# module_vs1053.net
KiCad netlist of a schematic drawn in EAGLE
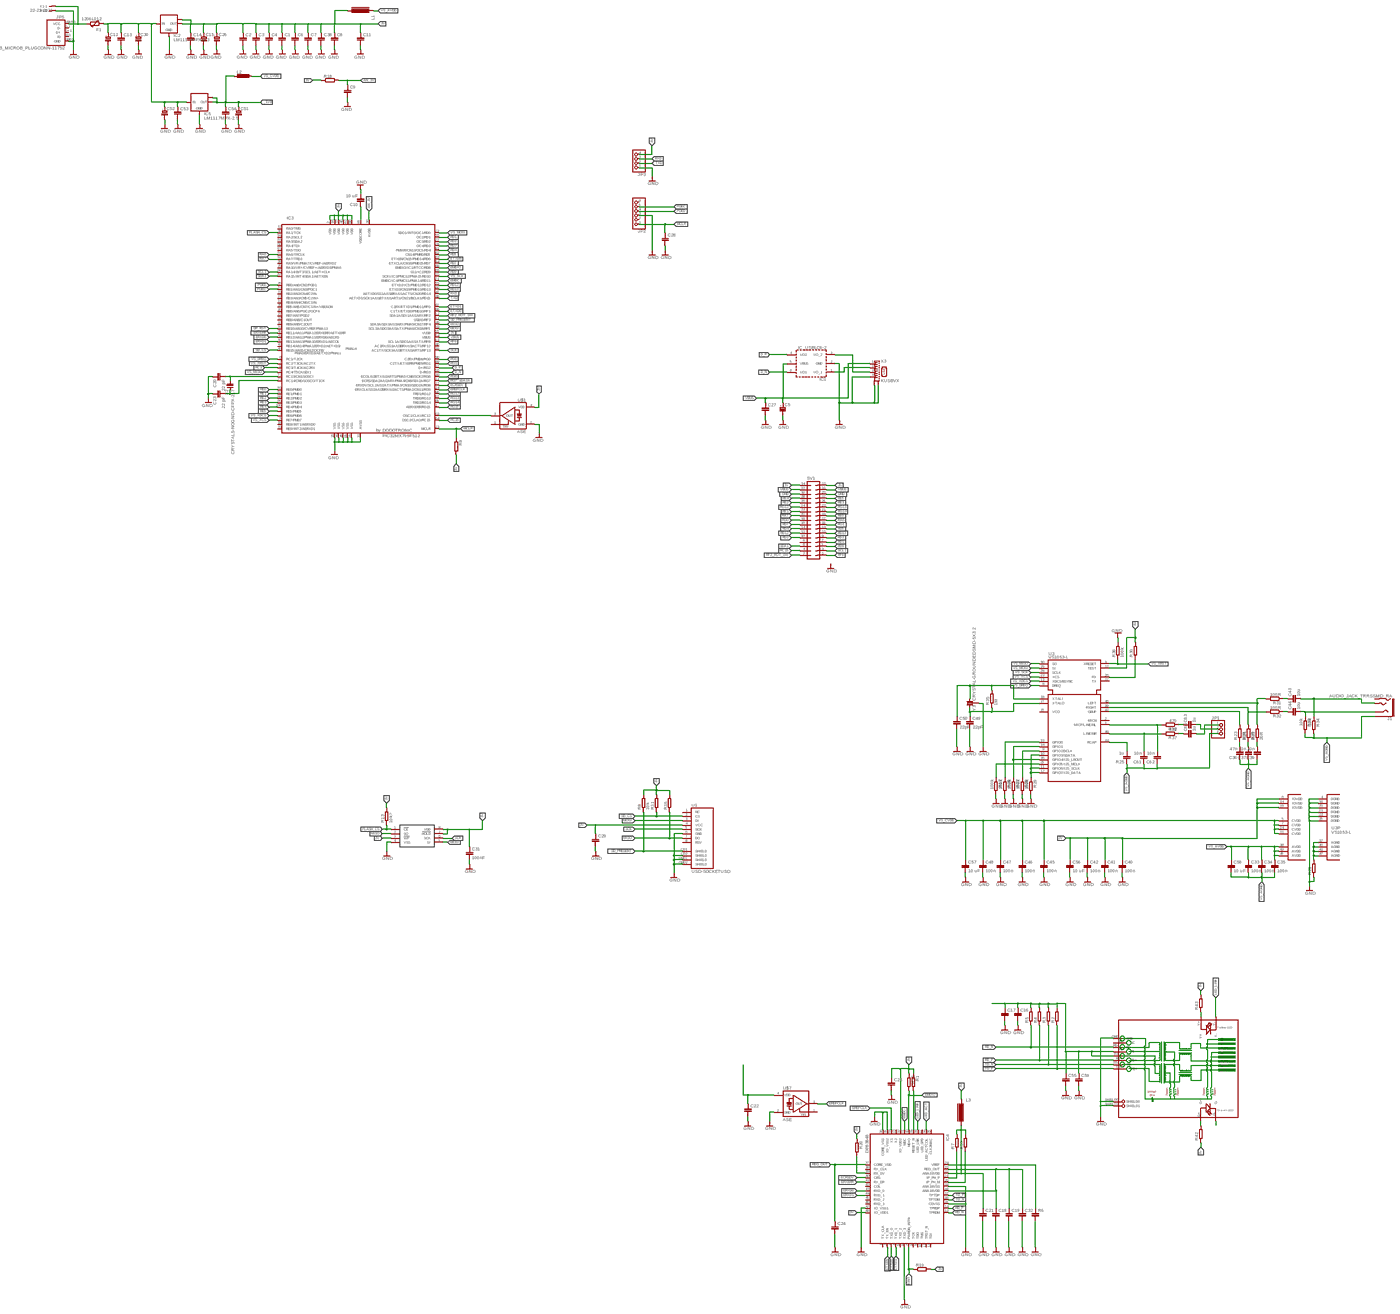
[diagram p0: schematic, sheet 1, overview]
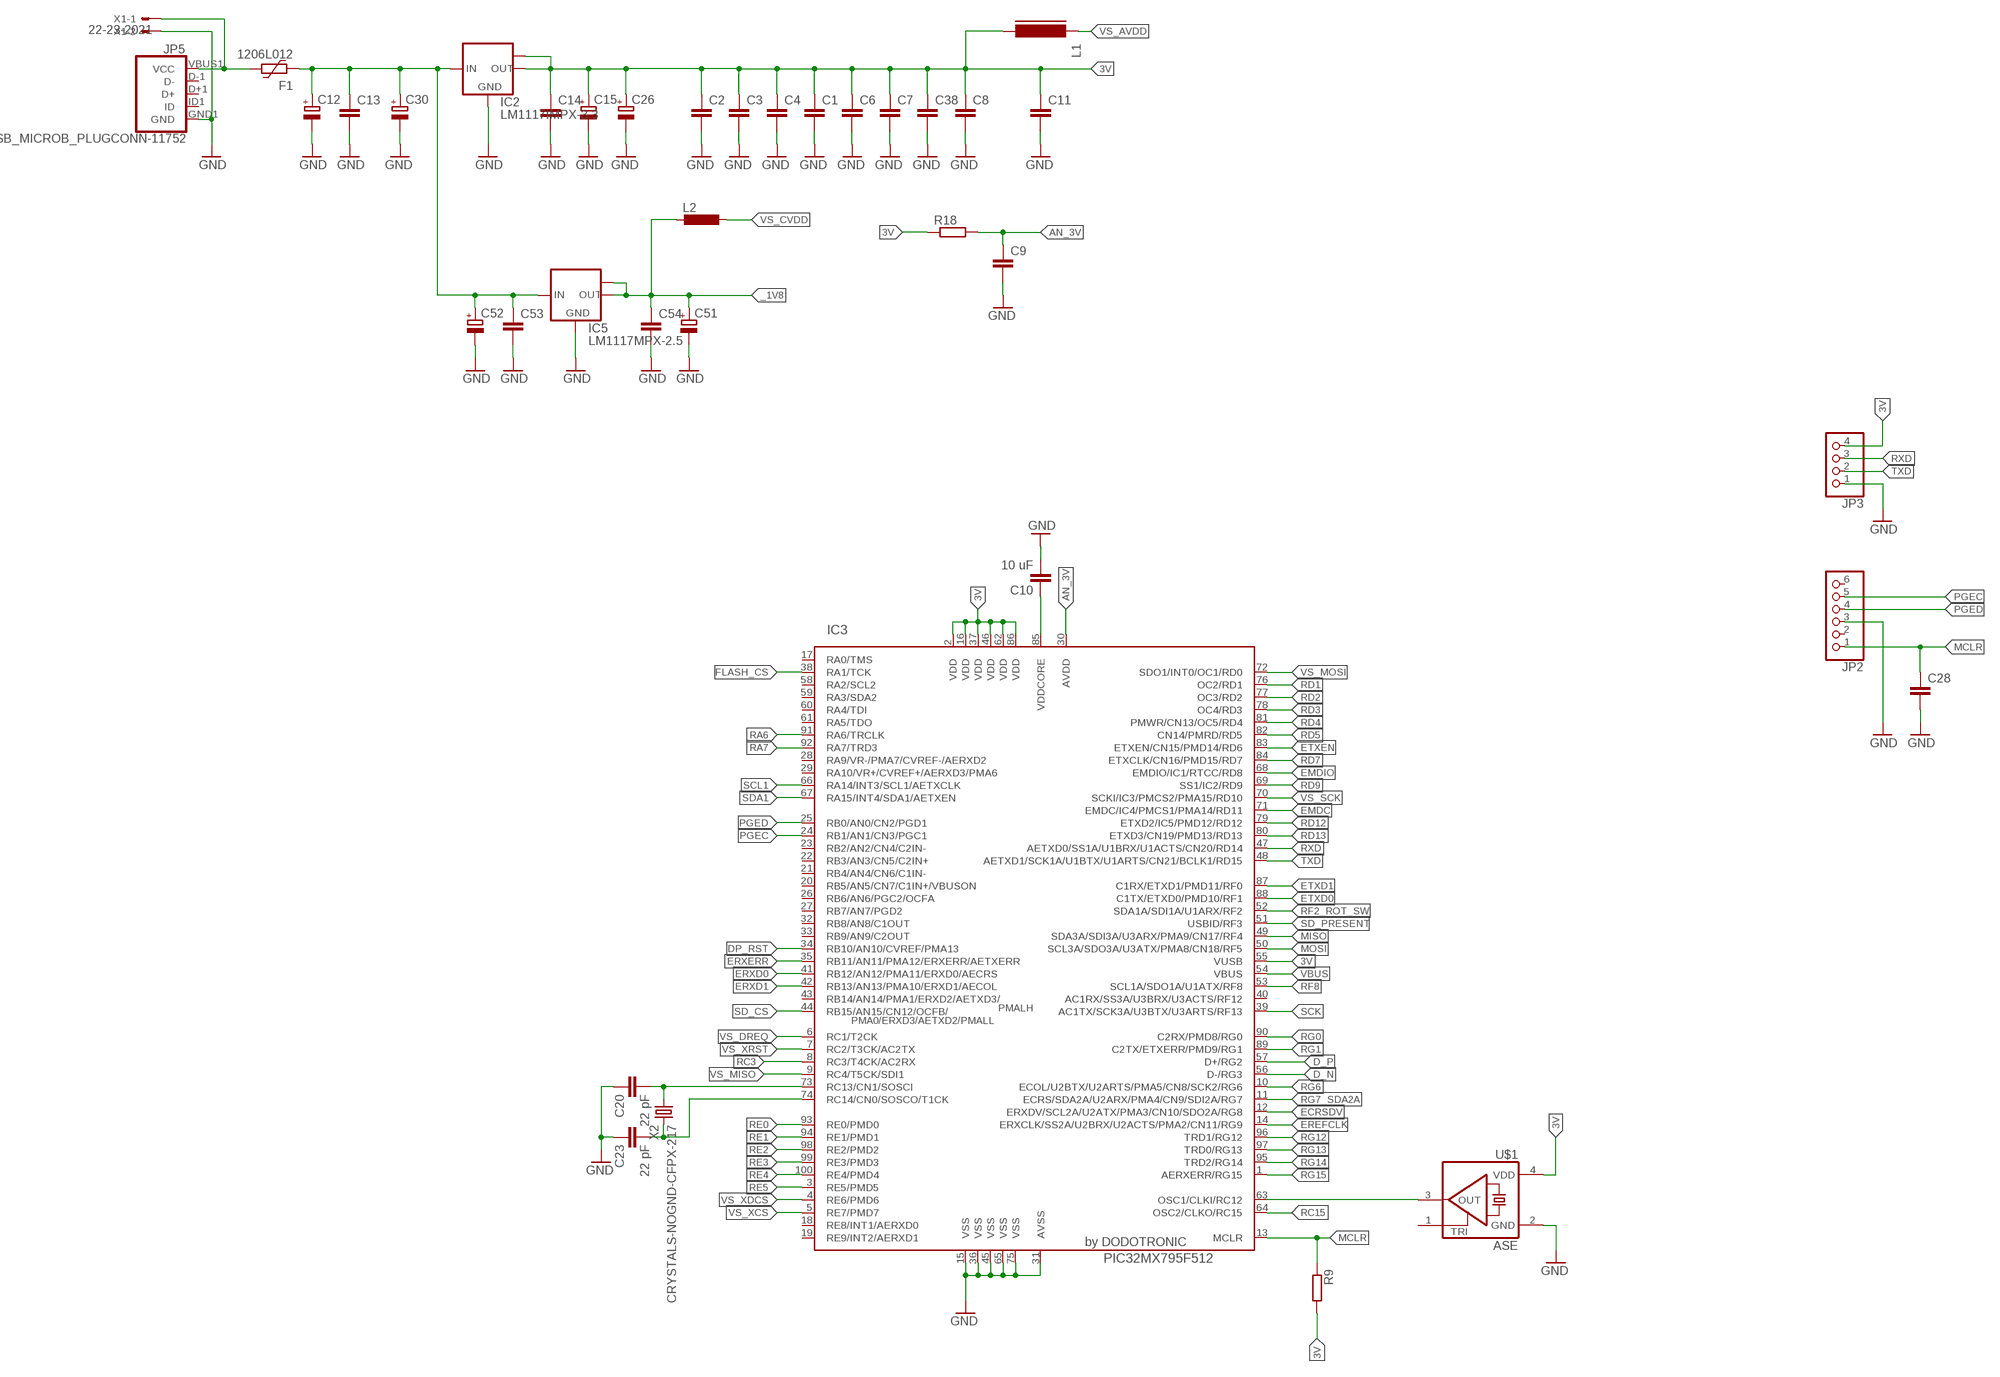
[diagram p1: schematic, sheet 1, part 1 of 4]
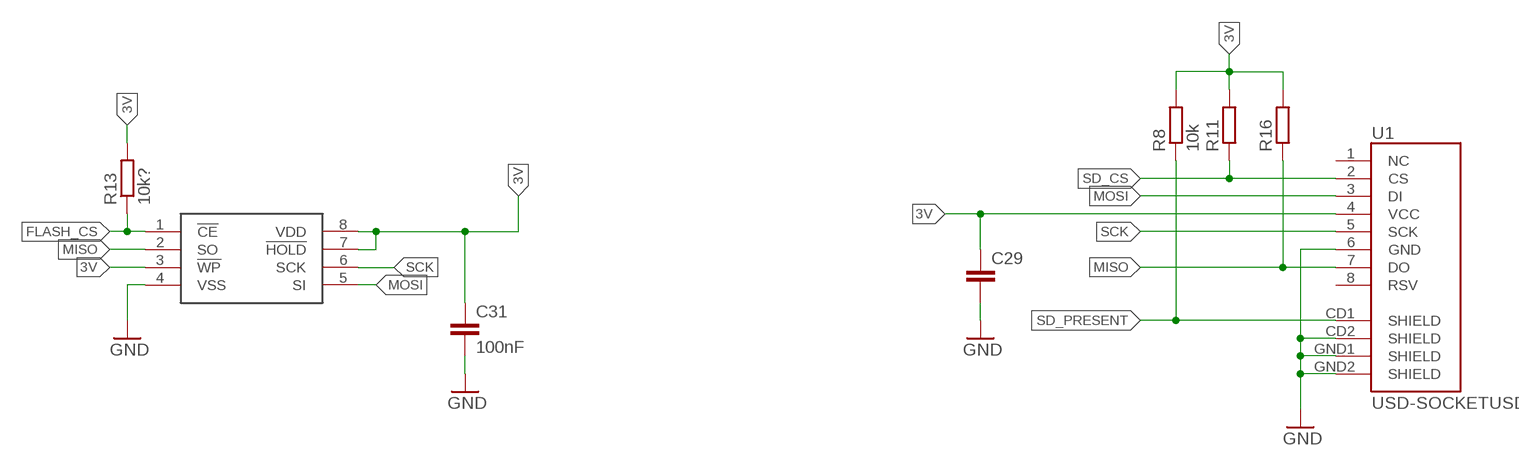
[diagram p2: schematic, sheet 1, part 2 of 4]
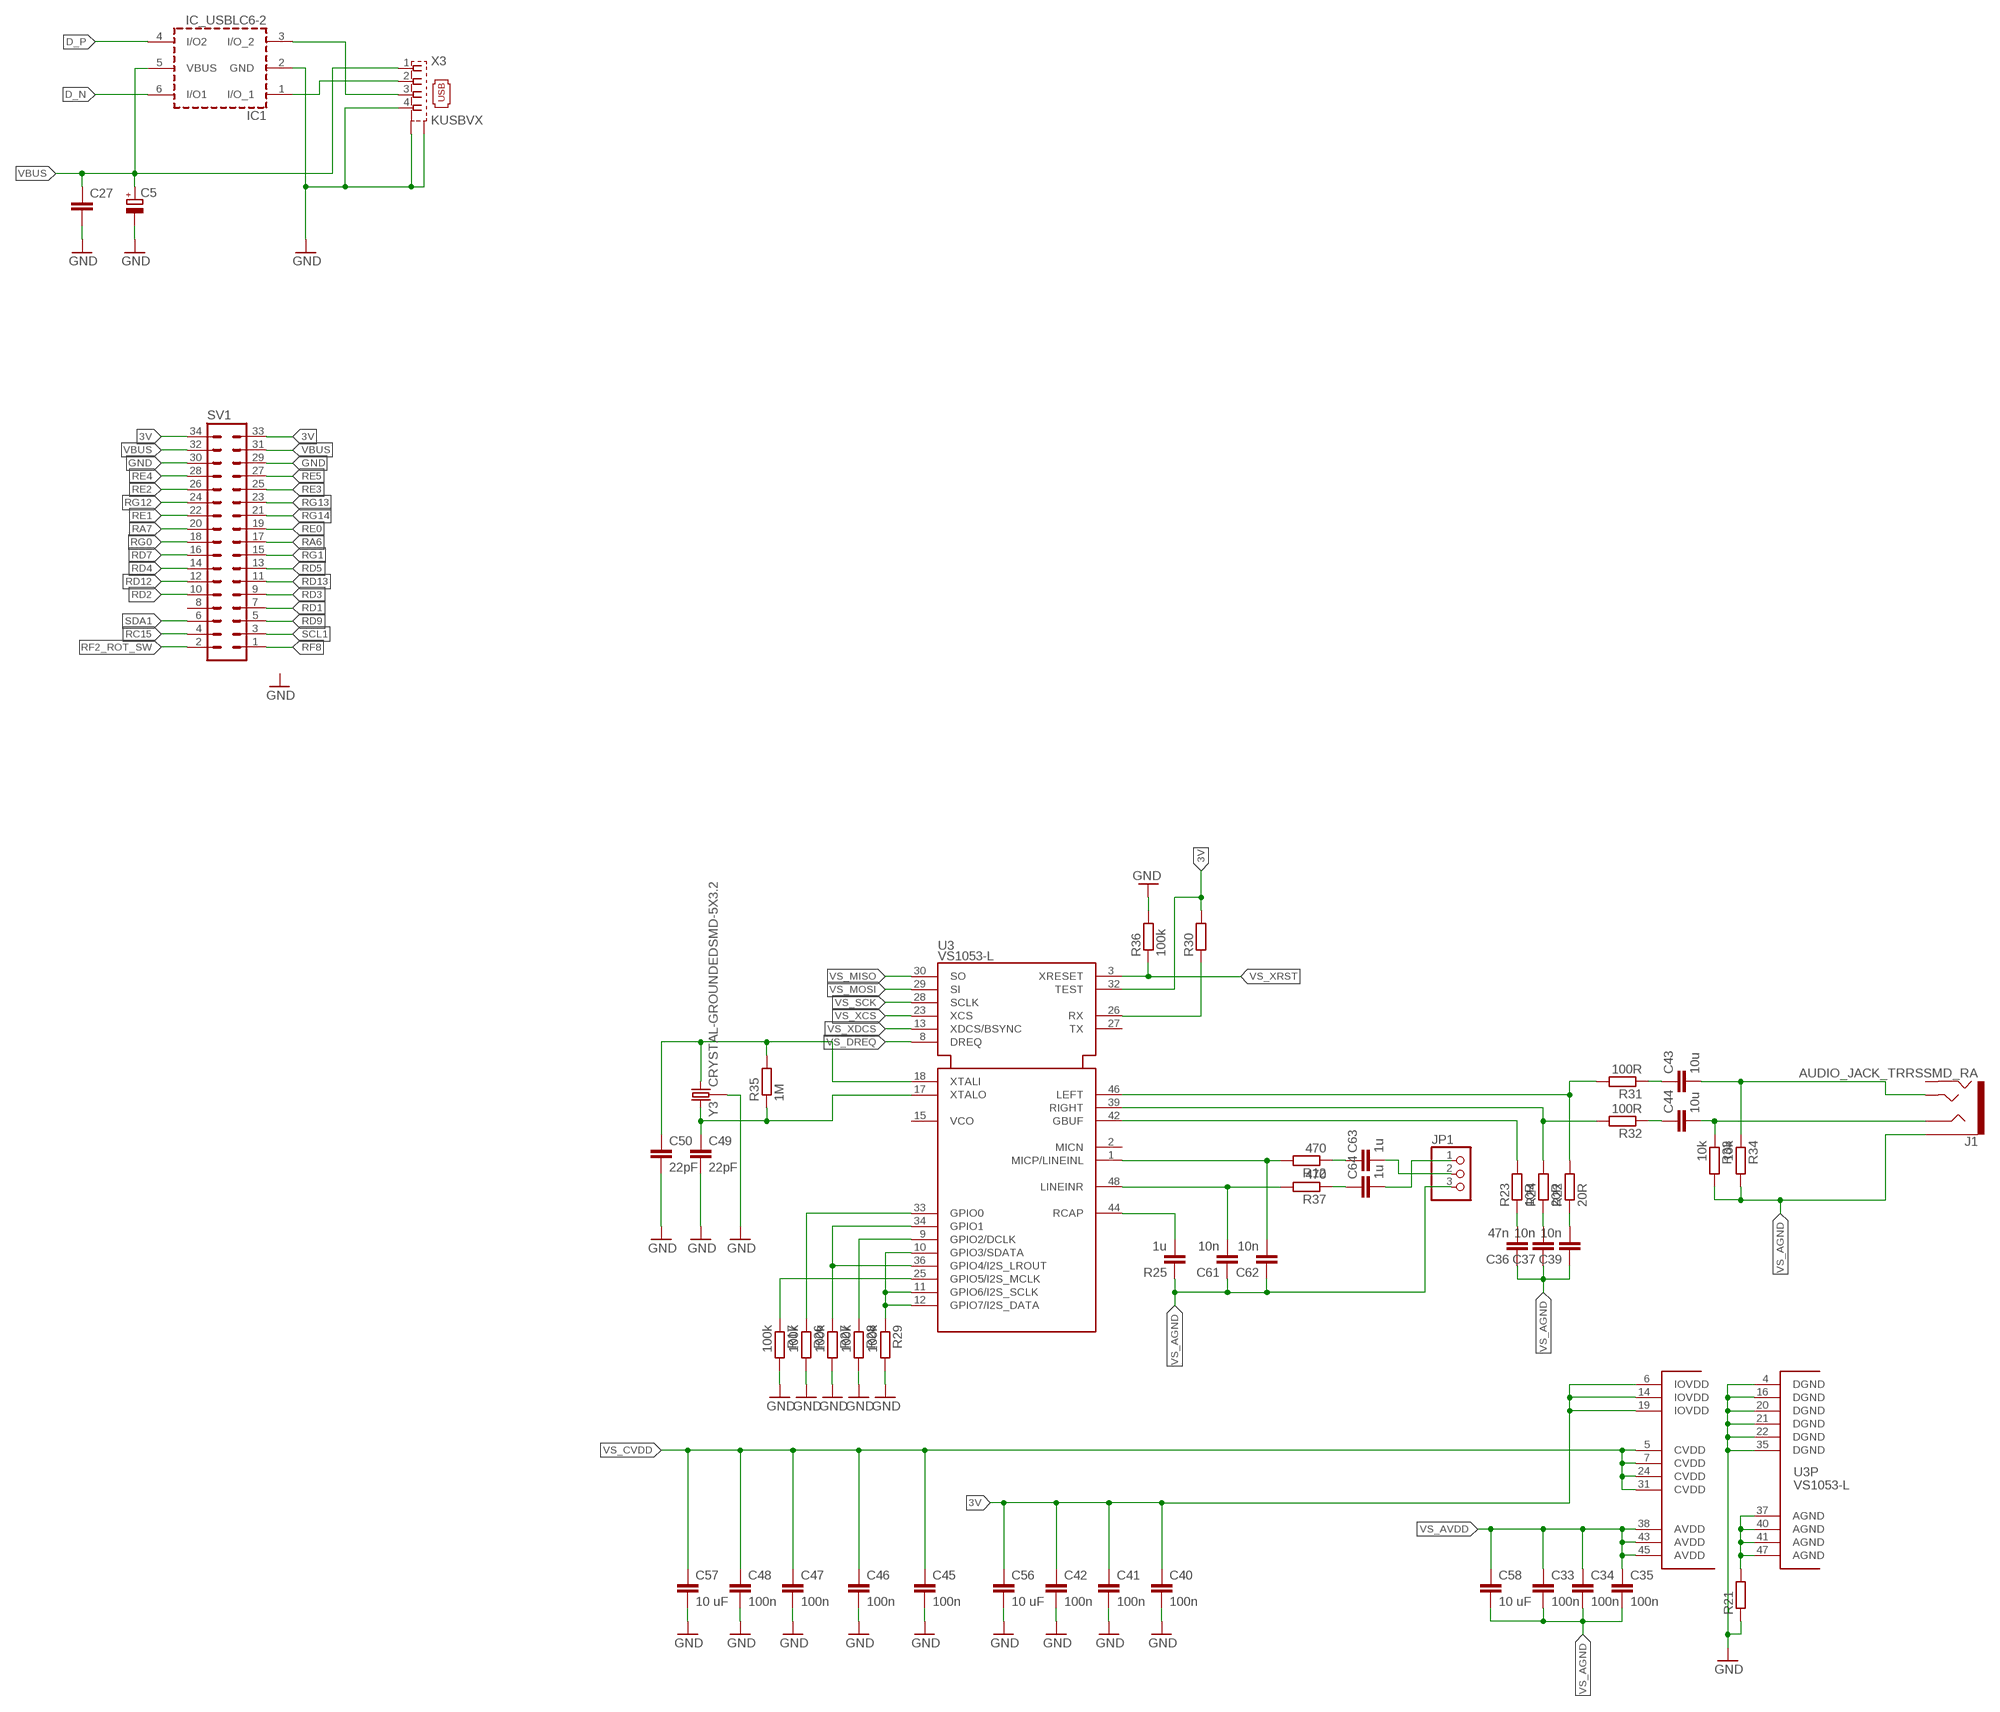
[diagram p3: schematic, sheet 1, part 3 of 4]
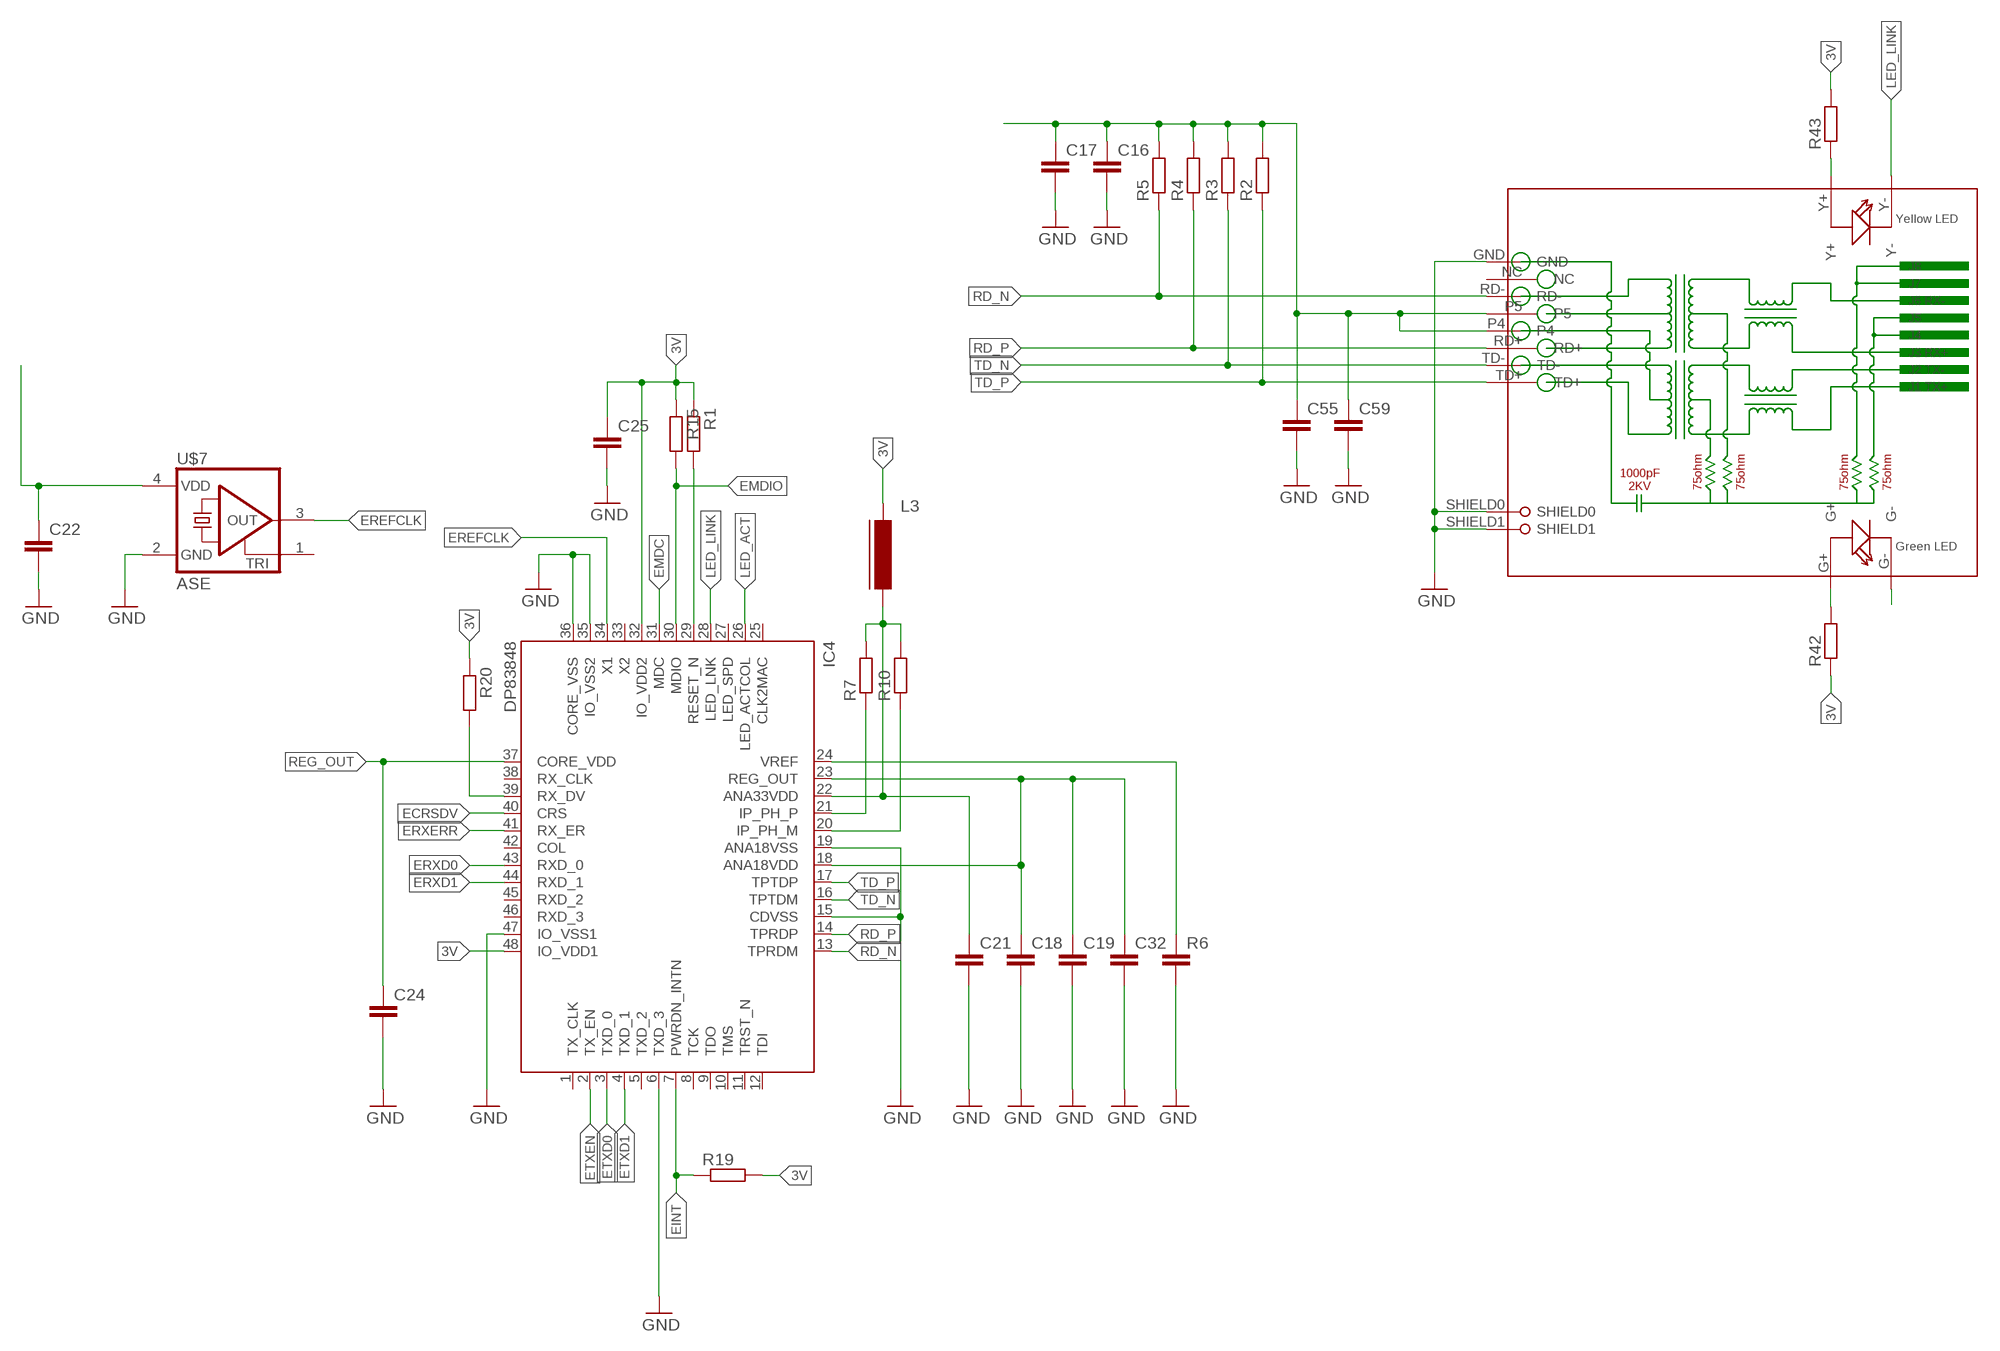
[diagram p4: schematic, sheet 1, part 4 of 4]

(export (version "E")
  (design (tool "Eeschema 10.0.6"))
  (components
    (comp (ref "C1")
      (value "C-EUC0402")
      (footprint "eagle-import:C0402")
      (libsource (lib "eagle-import") (part "C-EUC0402"))
    )
    (comp (ref "C2")
      (value "C-EUC0402")
      (footprint "eagle-import:C0402")
      (libsource (lib "eagle-import") (part "C-EUC0402"))
    )
    (comp (ref "C3")
      (value "C-EUC0402")
      (footprint "eagle-import:C0402")
      (libsource (lib "eagle-import") (part "C-EUC0402"))
    )
    (comp (ref "C4")
      (value "C-EUC0402")
      (footprint "eagle-import:C0402")
      (libsource (lib "eagle-import") (part "C-EUC0402"))
    )
    (comp (ref "C5")
      (value "CPOL-EUSMCA")
      (footprint "eagle-import:SMC_A")
      (libsource (lib "eagle-import") (part "CPOL-EUSMCA"))
    )
    (comp (ref "C6")
      (value "C-EUC0402")
      (footprint "eagle-import:C0402")
      (libsource (lib "eagle-import") (part "C-EUC0402"))
    )
    (comp (ref "C7")
      (value "C-EUC0402")
      (footprint "eagle-import:C0402")
      (libsource (lib "eagle-import") (part "C-EUC0402"))
    )
    (comp (ref "C8")
      (value "C-EUC0402")
      (footprint "eagle-import:C0402")
      (libsource (lib "eagle-import") (part "C-EUC0402"))
    )
    (comp (ref "C9")
      (value "C-EUC0402")
      (footprint "eagle-import:C0402")
      (libsource (lib "eagle-import") (part "C-EUC0402"))
    )
    (comp (ref "C10")
      (value "10 uF")
      (footprint "eagle-import:C0603")
      (libsource (lib "eagle-import") (part "C-EUC0603"))
    )
    (comp (ref "C11")
      (value "C-EUC0402")
      (footprint "eagle-import:C0402")
      (libsource (lib "eagle-import") (part "C-EUC0402"))
    )
    (comp (ref "C12")
      (value "CPOL-EUSMCB")
      (footprint "eagle-import:SMC_B")
      (libsource (lib "eagle-import") (part "CPOL-EUSMCB"))
    )
    (comp (ref "C13")
      (value "C-EUC0603")
      (footprint "eagle-import:C0603")
      (libsource (lib "eagle-import") (part "C-EUC0603"))
    )
    (comp (ref "C14")
      (value "C-EUC0603")
      (footprint "eagle-import:C0603")
      (libsource (lib "eagle-import") (part "C-EUC0603"))
    )
    (comp (ref "C15")
      (value "CPOL-EUSMCB")
      (footprint "eagle-import:SMC_B")
      (libsource (lib "eagle-import") (part "CPOL-EUSMCB"))
    )
    (comp (ref "C16")
      (value "C-EUC0603")
      (footprint "eagle-import:C0603")
      (libsource (lib "eagle-import") (part "C-EUC0603"))
    )
    (comp (ref "C17")
      (value "C-EUC0603")
      (footprint "eagle-import:C0603")
      (libsource (lib "eagle-import") (part "C-EUC0603"))
    )
    (comp (ref "C18")
      (value "C-EUC0402")
      (footprint "eagle-import:C0402")
      (libsource (lib "eagle-import") (part "C-EUC0402"))
    )
    (comp (ref "C19")
      (value "C-EUC0402")
      (footprint "eagle-import:C0402")
      (libsource (lib "eagle-import") (part "C-EUC0402"))
    )
    (comp (ref "C20")
      (value "22 pF")
      (footprint "eagle-import:C0603")
      (libsource (lib "eagle-import") (part "C-EUC0603"))
    )
    (comp (ref "C21")
      (value "C-EUC0402")
      (footprint "eagle-import:C0402")
      (libsource (lib "eagle-import") (part "C-EUC0402"))
    )
    (comp (ref "C22")
      (value "C-EUC0402")
      (footprint "eagle-import:C0402")
      (libsource (lib "eagle-import") (part "C-EUC0402"))
    )
    (comp (ref "C23")
      (value "22 pF")
      (footprint "eagle-import:C0603")
      (libsource (lib "eagle-import") (part "C-EUC0603"))
    )
    (comp (ref "C24")
      (value "C-EUC0603")
      (footprint "eagle-import:C0603")
      (libsource (lib "eagle-import") (part "C-EUC0603"))
    )
    (comp (ref "C25")
      (value "C-EUC0603")
      (footprint "eagle-import:C0603")
      (libsource (lib "eagle-import") (part "C-EUC0603"))
    )
    (comp (ref "C26")
      (value "CPOL-EUSMCA")
      (footprint "eagle-import:SMC_A")
      (libsource (lib "eagle-import") (part "CPOL-EUSMCA"))
    )
    (comp (ref "C27")
      (value "C-EUC0603")
      (footprint "eagle-import:C0603")
      (libsource (lib "eagle-import") (part "C-EUC0603"))
    )
    (comp (ref "C28")
      (value "C-EUC0603")
      (footprint "eagle-import:C0603")
      (libsource (lib "eagle-import") (part "C-EUC0603"))
    )
    (comp (ref "C29")
      (value "C-EUC0603")
      (footprint "eagle-import:C0603")
      (libsource (lib "eagle-import") (part "C-EUC0603"))
    )
    (comp (ref "C30")
      (value "CPOL-EUSMCA")
      (footprint "eagle-import:SMC_A")
      (libsource (lib "eagle-import") (part "CPOL-EUSMCA"))
    )
    (comp (ref "C31")
      (value "100nF")
      (footprint "eagle-import:C0603")
      (libsource (lib "eagle-import") (part "C-EUC0603"))
    )
    (comp (ref "C32")
      (value "C-EUC0603")
      (footprint "eagle-import:C0603")
      (libsource (lib "eagle-import") (part "C-EUC0603"))
    )
    (comp (ref "C33")
      (value "100n")
      (footprint "eagle-import:C0603")
      (libsource (lib "eagle-import") (part "C-EUC0603"))
    )
    (comp (ref "C34")
      (value "100n")
      (footprint "eagle-import:C0603")
      (libsource (lib "eagle-import") (part "C-EUC0603"))
    )
    (comp (ref "C35")
      (value "100n")
      (footprint "eagle-import:C0603")
      (libsource (lib "eagle-import") (part "C-EUC0603"))
    )
    (comp (ref "C36")
      (value "47n")
      (footprint "eagle-import:C0603")
      (libsource (lib "eagle-import") (part "C-EUC0603"))
    )
    (comp (ref "C37")
      (value "10n")
      (footprint "eagle-import:C0603")
      (libsource (lib "eagle-import") (part "C-EUC0603"))
    )
    (comp (ref "C38")
      (value "C-EUC0402")
      (footprint "eagle-import:C0402")
      (libsource (lib "eagle-import") (part "C-EUC0402"))
    )
    (comp (ref "C39")
      (value "10n")
      (footprint "eagle-import:C0603")
      (libsource (lib "eagle-import") (part "C-EUC0603"))
    )
    (comp (ref "C40")
      (value "100n")
      (footprint "eagle-import:C0402")
      (libsource (lib "eagle-import") (part "C-EUC0402"))
    )
    (comp (ref "C41")
      (value "100n")
      (footprint "eagle-import:C0402")
      (libsource (lib "eagle-import") (part "C-EUC0402"))
    )
    (comp (ref "C42")
      (value "100n")
      (footprint "eagle-import:C0402")
      (libsource (lib "eagle-import") (part "C-EUC0402"))
    )
    (comp (ref "C43")
      (value "10u")
      (footprint "eagle-import:C0603")
      (libsource (lib "eagle-import") (part "C-EUC0603"))
    )
    (comp (ref "C44")
      (value "10u")
      (footprint "eagle-import:C0603")
      (libsource (lib "eagle-import") (part "C-EUC0603"))
    )
    (comp (ref "C45")
      (value "100n")
      (footprint "eagle-import:C0402")
      (libsource (lib "eagle-import") (part "C-EUC0402"))
    )
    (comp (ref "C46")
      (value "100n")
      (footprint "eagle-import:C0603")
      (libsource (lib "eagle-import") (part "C-EUC0603"))
    )
    (comp (ref "C47")
      (value "100n")
      (footprint "eagle-import:C0603")
      (libsource (lib "eagle-import") (part "C-EUC0603"))
    )
    (comp (ref "C48")
      (value "100n")
      (footprint "eagle-import:C0603")
      (libsource (lib "eagle-import") (part "C-EUC0603"))
    )
    (comp (ref "C49")
      (value "22pF")
      (footprint "eagle-import:C0603")
      (libsource (lib "eagle-import") (part "C-EUC0603"))
    )
    (comp (ref "C50")
      (value "22pF")
      (footprint "eagle-import:C0603")
      (libsource (lib "eagle-import") (part "C-EUC0603"))
    )
    (comp (ref "C51")
      (value "CPOL-EUSMCB")
      (footprint "eagle-import:SMC_B")
      (libsource (lib "eagle-import") (part "CPOL-EUSMCB"))
    )
    (comp (ref "C52")
      (value "CPOL-EUSMCB")
      (footprint "eagle-import:SMC_B")
      (libsource (lib "eagle-import") (part "CPOL-EUSMCB"))
    )
    (comp (ref "C53")
      (value "C-EUC1206")
      (footprint "eagle-import:C1206")
      (libsource (lib "eagle-import") (part "C-EUC1206"))
    )
    (comp (ref "C54")
      (value "C-EUC1206")
      (footprint "eagle-import:C1206")
      (libsource (lib "eagle-import") (part "C-EUC1206"))
    )
    (comp (ref "C55")
      (value "C-EUC0603")
      (footprint "eagle-import:C0603")
      (libsource (lib "eagle-import") (part "C-EUC0603"))
    )
    (comp (ref "C56")
      (value "10 uF")
      (footprint "eagle-import:C0603")
      (libsource (lib "eagle-import") (part "C-EUC0603"))
    )
    (comp (ref "C57")
      (value "10 uF")
      (footprint "eagle-import:C0603")
      (libsource (lib "eagle-import") (part "C-EUC0603"))
    )
    (comp (ref "C58")
      (value "10 uF")
      (footprint "eagle-import:C0603")
      (libsource (lib "eagle-import") (part "C-EUC0603"))
    )
    (comp (ref "C59")
      (value "C-EUC0603")
      (footprint "eagle-import:C0603")
      (libsource (lib "eagle-import") (part "C-EUC0603"))
    )
    (comp (ref "C61")
      (value "10n")
      (footprint "eagle-import:C0603")
      (libsource (lib "eagle-import") (part "C-EUC0603"))
    )
    (comp (ref "C62")
      (value "10n")
      (footprint "eagle-import:C0603")
      (libsource (lib "eagle-import") (part "C-EUC0603"))
    )
    (comp (ref "C63")
      (value "1u")
      (footprint "eagle-import:C0603")
      (libsource (lib "eagle-import") (part "C-EUC0603"))
    )
    (comp (ref "C64")
      (value "1u")
      (footprint "eagle-import:C0603")
      (libsource (lib "eagle-import") (part "C-EUC0603"))
    )
    (comp (ref "F1")
      (value "1206L012")
      (footprint "eagle-import:1206L")
      (fields (field (name "MF") "Littelfuse"))
      (libsource (lib "eagle-import") (part "?1206L012"))
    )
    (comp (ref "IC1")
      (value "IC_USBLC6-2")
      (footprint "eagle-import:SOT-23-6L")
      (libsource (lib "eagle-import") (part "IC_USBLC6-2"))
    )
    (comp (ref "IC2")
      (value "LM1117IMPX-3.3")
      (footprint "eagle-import:SOT223")
      (libsource (lib "eagle-import") (part "LM1117IMPX-3.3"))
    )
    (comp (ref "IC3")
      (value "PIC32MX795F512")
      (footprint "eagle-import:TQFP100_12X12")
      (libsource (lib "eagle-import") (part "PIC32MX795F512"))
    )
    (comp (ref "IC4")
      (value "DP83848")
      (footprint "eagle-import:LQFP48")
      (fields (field (name "MPN") "DP83848VYB"))
      (libsource (lib "eagle-import") (part "DP83848"))
    )
    (comp (ref "IC5")
      (value "LM1117MPX-2.5")
      (footprint "eagle-import:SOT223")
      (libsource (lib "eagle-import") (part "LM1117MPX-2.5"))
    )
    (comp (ref "J1")
      (value "AUDIO_JACK_TRRSSMD_RA")
      (footprint "eagle-import:AUDIO_JACK_3.5MM_TRRS_SMD_RA")
      (libsource (lib "eagle-import") (part "AUDIO_JACK_TRRSSMD_RA"))
    )
    (comp (ref "JP1")
      (value "PINHD-1X3")
      (footprint "eagle-import:1X03")
      (libsource (lib "eagle-import") (part "PINHD-1X3"))
    )
    (comp (ref "JP2")
      (value "PINHD-1X6")
      (footprint "eagle-import:1X06")
      (libsource (lib "eagle-import") (part "PINHD-1X6"))
    )
    (comp (ref "JP3")
      (value "PINHD-1X4")
      (footprint "eagle-import:1X04")
      (libsource (lib "eagle-import") (part "PINHD-1X4"))
    )
    (comp (ref "JP5")
      (value "USB_MICROB_PLUGCONN-11752")
      (footprint "eagle-import:USB-B-MICRO-SMD_V03")
      (libsource (lib "eagle-import") (part "USB_MICROB_PLUGCONN-11752"))
    )
    (comp (ref "L1")
      (value "FERRITE-0805")
      (footprint "eagle-import:FB805")
      (libsource (lib "eagle-import") (part "FERRITE-0805"))
    )
    (comp (ref "L2")
      (value "L-EU0204/7")
      (footprint "eagle-import:0204_7")
      (libsource (lib "eagle-import") (part "L-EU0204/7"))
    )
    (comp (ref "L3")
      (value "FERRITE-0805")
      (footprint "eagle-import:FB805")
      (libsource (lib "eagle-import") (part "FERRITE-0805"))
    )
    (comp (ref "R1")
      (value "R-EU_R0402")
      (footprint "eagle-import:R0402")
      (libsource (lib "eagle-import") (part "R-EU_R0402"))
    )
    (comp (ref "R2")
      (value "R-EU_R0603")
      (footprint "eagle-import:R0603")
      (libsource (lib "eagle-import") (part "R-EU_R0603"))
    )
    (comp (ref "R3")
      (value "R-EU_R0603")
      (footprint "eagle-import:R0603")
      (libsource (lib "eagle-import") (part "R-EU_R0603"))
    )
    (comp (ref "R4")
      (value "R-EU_R0603")
      (footprint "eagle-import:R0603")
      (libsource (lib "eagle-import") (part "R-EU_R0603"))
    )
    (comp (ref "R5")
      (value "R-EU_R0603")
      (footprint "eagle-import:R0603")
      (libsource (lib "eagle-import") (part "R-EU_R0603"))
    )
    (comp (ref "R6")
      (value "C-EUC0603")
      (footprint "eagle-import:C0603")
      (libsource (lib "eagle-import") (part "C-EUC0603"))
    )
    (comp (ref "R7")
      (value "R-EU_R0402")
      (footprint "eagle-import:R0402")
      (libsource (lib "eagle-import") (part "R-EU_R0402"))
    )
    (comp (ref "R8")
      (value "10k")
      (footprint "eagle-import:R0603")
      (libsource (lib "eagle-import") (part "R-EU_R0603"))
    )
    (comp (ref "R9")
      (value "R-EU_R0603")
      (footprint "eagle-import:R0603")
      (libsource (lib "eagle-import") (part "R-EU_R0603"))
    )
    (comp (ref "R10")
      (value "R-EU_R0402")
      (footprint "eagle-import:R0402")
      (libsource (lib "eagle-import") (part "R-EU_R0402"))
    )
    (comp (ref "R11")
      (value "R-EU_R0603")
      (footprint "eagle-import:R0603")
      (libsource (lib "eagle-import") (part "R-EU_R0603"))
    )
    (comp (ref "R12")
      (value "470")
      (footprint "eagle-import:0204_7")
      (libsource (lib "eagle-import") (part "R-EU_0204/7"))
    )
    (comp (ref "R13")
      (value "10k?")
      (footprint "eagle-import:R0603")
      (libsource (lib "eagle-import") (part "R-EU_R0603"))
    )
    (comp (ref "R15")
      (value "R-EU_R0603")
      (footprint "eagle-import:R0603")
      (libsource (lib "eagle-import") (part "R-EU_R0603"))
    )
    (comp (ref "R16")
      (value "R-EU_R0603")
      (footprint "eagle-import:R0603")
      (libsource (lib "eagle-import") (part "R-EU_R0603"))
    )
    (comp (ref "R17")
      (value "100k")
      (footprint "eagle-import:R0402")
      (libsource (lib "eagle-import") (part "R-EU_R0402"))
    )
    (comp (ref "R18")
      (value "R-EU_R0805")
      (footprint "eagle-import:R0805")
      (libsource (lib "eagle-import") (part "R-EU_R0805"))
    )
    (comp (ref "R19")
      (value "R-EU_R0402")
      (footprint "eagle-import:R0402")
      (libsource (lib "eagle-import") (part "R-EU_R0402"))
    )
    (comp (ref "R20")
      (value "R-EU_R0603")
      (footprint "eagle-import:R0603")
      (libsource (lib "eagle-import") (part "R-EU_R0603"))
    )
    (comp (ref "R21")
      (value "R-EU_R0603")
      (footprint "eagle-import:R0603")
      (libsource (lib "eagle-import") (part "R-EU_R0603"))
    )
    (comp (ref "R22")
      (value "20R")
      (footprint "eagle-import:R0603")
      (libsource (lib "eagle-import") (part "R-EU_R0603"))
    )
    (comp (ref "R23")
      (value "10R")
      (footprint "eagle-import:R0603")
      (libsource (lib "eagle-import") (part "R-EU_R0603"))
    )
    (comp (ref "R24")
      (value "20R")
      (footprint "eagle-import:R0603")
      (libsource (lib "eagle-import") (part "R-EU_R0603"))
    )
    (comp (ref "R25")
      (value "1u")
      (footprint "eagle-import:C0603")
      (libsource (lib "eagle-import") (part "C-EUC0603"))
    )
    (comp (ref "R26")
      (value "100k")
      (footprint "eagle-import:R0402")
      (libsource (lib "eagle-import") (part "R-EU_R0402"))
    )
    (comp (ref "R27")
      (value "100k")
      (footprint "eagle-import:R0402")
      (libsource (lib "eagle-import") (part "R-EU_R0402"))
    )
    (comp (ref "R28")
      (value "100k")
      (footprint "eagle-import:R0402")
      (libsource (lib "eagle-import") (part "R-EU_R0402"))
    )
    (comp (ref "R29")
      (value "100k")
      (footprint "eagle-import:R0402")
      (libsource (lib "eagle-import") (part "R-EU_R0402"))
    )
    (comp (ref "R30")
      (value "R-EU_0204/7")
      (footprint "eagle-import:0204_7")
      (libsource (lib "eagle-import") (part "R-EU_0204/7"))
    )
    (comp (ref "R31")
      (value "100R")
      (footprint "eagle-import:R0603")
      (libsource (lib "eagle-import") (part "R-EU_R0603"))
    )
    (comp (ref "R32")
      (value "100R")
      (footprint "eagle-import:R0603")
      (libsource (lib "eagle-import") (part "R-EU_R0603"))
    )
    (comp (ref "R33")
      (value "10k")
      (footprint "eagle-import:R0603")
      (libsource (lib "eagle-import") (part "R-EU_R0603"))
    )
    (comp (ref "R34")
      (value "10k")
      (footprint "eagle-import:R0603")
      (libsource (lib "eagle-import") (part "R-EU_R0603"))
    )
    (comp (ref "R35")
      (value "1M")
      (footprint "eagle-import:R0603")
      (libsource (lib "eagle-import") (part "R-EU_R0603"))
    )
    (comp (ref "R36")
      (value "100k")
      (footprint "eagle-import:R0603")
      (libsource (lib "eagle-import") (part "R-EU_R0603"))
    )
    (comp (ref "R37")
      (value "470")
      (footprint "eagle-import:0204_7")
      (libsource (lib "eagle-import") (part "R-EU_0204/7"))
    )
    (comp (ref "R42")
      (value "R-EU_R0603")
      (footprint "eagle-import:R0603")
      (libsource (lib "eagle-import") (part "R-EU_R0603"))
    )
    (comp (ref "R43")
      (value "R-EU_R0603")
      (footprint "eagle-import:R0603")
      (libsource (lib "eagle-import") (part "R-EU_R0603"))
    )
    (comp (ref "RJ1")
      (value "HR911105A")
      (footprint "eagle-import:HR911105A")
      (libsource (lib "eagle-import") (part "HR911105A"))
    )
    (comp (ref "SV1")
      (value "ML34L")
      (footprint "eagle-import:ML34L")
      (libsource (lib "eagle-import") (part "ML34L"))
    )
    (comp (ref "U$1")
      (value "ASE")
      (footprint "eagle-import:ASE")
      (libsource (lib "eagle-import") (part "ASE"))
    )
    (comp (ref "U$2")
      (value "SST25VF016BSO8M")
      (footprint "eagle-import:SO-08M")
      (libsource (lib "eagle-import") (part "SST25VF016BSO8M"))
    )
    (comp (ref "U$7")
      (value "ASE")
      (footprint "eagle-import:ASE")
      (libsource (lib "eagle-import") (part "ASE"))
    )
    (comp (ref "U1")
      (value "USD-SOCKETUSD")
      (footprint "eagle-import:USD-SOCKET-PP")
      (libsource (lib "eagle-import") (part "USD-SOCKETUSD"))
    )
    (comp (ref "U3")
      (value "VS1053-L")
      (footprint "eagle-import:LQFP48")
      (libsource (lib "eagle-import") (part "VS1053-L"))
    )
    (comp (ref "X1")
      (value "22-23-2021")
      (footprint "eagle-import:22-23-2021")
      (fields (field (name "MF") "MOLEX"))
      (libsource (lib "eagle-import") (part "22-23-2021"))
    )
    (comp (ref "X2")
      (value "CRYSTALS-NOGND-CFPX-217")
      (footprint "eagle-import:3.2X1.5-2-PAD")
      (libsource (lib "eagle-import") (part "CRYSTALS-NOGND-CFPX-217"))
    )
    (comp (ref "X3")
      (value "KUSBVX")
      (footprint "eagle-import:KUSBVX")
      (libsource (lib "eagle-import") (part "KUSBVX"))
    )
    (comp (ref "Y3")
      (value "CRYSTAL-GROUNDEDSMD-5X3.2")
      (footprint "eagle-import:CRYSTAL-SMD-5X3.2-4PAD")
      (libsource (lib "eagle-import") (part "CRYSTAL-GROUNDEDSMD-5X3.2"))
    )
  )
  (nets
    (net (code "1") (name "/A3V") (class "Default")
      (node (ref "C16") (pin "1") (pinfunction "1_1") (pintype "passive"))
      (node (ref "C17") (pin "1") (pinfunction "1_1") (pintype "passive"))
      (node (ref "C21") (pin "1") (pinfunction "1_1") (pintype "passive"))
      (node (ref "C55") (pin "1") (pinfunction "1_1") (pintype "passive"))
      (node (ref "C59") (pin "1") (pinfunction "1_1") (pintype "passive"))
      (node (ref "IC4") (pin "22") (pinfunction "ANA33VDD_22") (pintype "power_in"))
      (node (ref "L3") (pin "2") (pinfunction "2_2") (pintype "passive"))
      (node (ref "R10") (pin "2") (pinfunction "2_2") (pintype "passive"))
      (node (ref "R2") (pin "2") (pinfunction "2_2") (pintype "passive"))
      (node (ref "R3") (pin "2") (pinfunction "2_2") (pintype "passive"))
      (node (ref "R4") (pin "2") (pinfunction "2_2") (pintype "passive"))
      (node (ref "R5") (pin "2") (pinfunction "2_2") (pintype "passive"))
      (node (ref "R7") (pin "2") (pinfunction "2_2") (pintype "passive"))
      (node (ref "RJ1") (pin "P4") (pinfunction "P4_P4") (pintype "bidirectional"))
      (node (ref "RJ1") (pin "P5") (pinfunction "P5_P5") (pintype "bidirectional"))
    )
    (net (code "2") (name "3V") (class "Default")
      (node (ref "C1") (pin "1") (pinfunction "1_1") (pintype "passive"))
      (node (ref "C11") (pin "1") (pinfunction "1_1") (pintype "passive"))
      (node (ref "C14") (pin "1") (pinfunction "1_1") (pintype "passive"))
      (node (ref "C15") (pin "+") (pinfunction "+_+") (pintype "passive"))
      (node (ref "C2") (pin "1") (pinfunction "1_1") (pintype "passive"))
      (node (ref "C22") (pin "1") (pinfunction "1_1") (pintype "passive"))
      (node (ref "C25") (pin "1") (pinfunction "1_1") (pintype "passive"))
      (node (ref "C26") (pin "+") (pinfunction "+_+") (pintype "passive"))
      (node (ref "C29") (pin "1") (pinfunction "1_1") (pintype "passive"))
      (node (ref "C3") (pin "1") (pinfunction "1_1") (pintype "passive"))
      (node (ref "C31") (pin "1") (pinfunction "1_1") (pintype "passive"))
      (node (ref "C38") (pin "1") (pinfunction "1_1") (pintype "passive"))
      (node (ref "C4") (pin "1") (pinfunction "1_1") (pintype "passive"))
      (node (ref "C40") (pin "1") (pinfunction "1_1") (pintype "passive"))
      (node (ref "C41") (pin "1") (pinfunction "1_1") (pintype "passive"))
      (node (ref "C42") (pin "1") (pinfunction "1_1") (pintype "passive"))
      (node (ref "C56") (pin "1") (pinfunction "1_1") (pintype "passive"))
      (node (ref "C6") (pin "1") (pinfunction "1_1") (pintype "passive"))
      (node (ref "C7") (pin "1") (pinfunction "1_1") (pintype "passive"))
      (node (ref "C8") (pin "1") (pinfunction "1_1") (pintype "passive"))
      (node (ref "IC2") (pin "2") (pinfunction "OUT_2") (pintype "passive"))
      (node (ref "IC2") (pin "TAB") (pinfunction "OUT1_TAB") (pintype "passive"))
      (node (ref "IC3") (pin "16") (pinfunction "VDD_16") (pintype "power_in"))
      (node (ref "IC3") (pin "2") (pinfunction "VDD_2") (pintype "power_in"))
      (node (ref "IC3") (pin "37") (pinfunction "VDD_37") (pintype "power_in"))
      (node (ref "IC3") (pin "46") (pinfunction "VDD_46") (pintype "power_in"))
      (node (ref "IC3") (pin "55") (pinfunction "VUSB_55") (pintype "bidirectional"))
      (node (ref "IC3") (pin "62") (pinfunction "VDD_62") (pintype "power_in"))
      (node (ref "IC3") (pin "86") (pinfunction "VDD_86") (pintype "power_in"))
      (node (ref "IC4") (pin "32") (pinfunction "IO_VDD2_32") (pintype "power_in"))
      (node (ref "IC4") (pin "48") (pinfunction "IO_VDD1_48") (pintype "power_in"))
      (node (ref "JP3") (pin "4") (pinfunction "4_4") (pintype "passive"))
      (node (ref "L1") (pin "2") (pinfunction "2_2") (pintype "passive"))
      (node (ref "L3") (pin "1") (pinfunction "1_1") (pintype "passive"))
      (node (ref "R1") (pin "1") (pinfunction "1_1") (pintype "passive"))
      (node (ref "R11") (pin "2") (pinfunction "2_2") (pintype "passive"))
      (node (ref "R13") (pin "2") (pinfunction "2_2") (pintype "passive"))
      (node (ref "R15") (pin "1") (pinfunction "1_1") (pintype "passive"))
      (node (ref "R16") (pin "2") (pinfunction "2_2") (pintype "passive"))
      (node (ref "R18") (pin "1") (pinfunction "1_1") (pintype "passive"))
      (node (ref "R19") (pin "2") (pinfunction "2_2") (pintype "passive"))
      (node (ref "R20") (pin "1") (pinfunction "1_1") (pintype "passive"))
      (node (ref "R30") (pin "2") (pinfunction "2_2") (pintype "passive"))
      (node (ref "R42") (pin "1") (pinfunction "1_1") (pintype "passive"))
      (node (ref "R43") (pin "2") (pinfunction "2_2") (pintype "passive"))
      (node (ref "R8") (pin "2") (pinfunction "2_2") (pintype "passive"))
      (node (ref "R9") (pin "2") (pinfunction "2_2") (pintype "passive"))
      (node (ref "SV1") (pin "33") (pinfunction "33_33") (pintype "passive"))
      (node (ref "SV1") (pin "34") (pinfunction "34_34") (pintype "passive"))
      (node (ref "U$1") (pin "4") (pinfunction "VDD_4") (pintype "power_in"))
      (node (ref "U$2") (pin "3") (pinfunction "~{WP}_3") (pintype "bidirectional"))
      (node (ref "U$2") (pin "7") (pinfunction "~{HOLD}_7") (pintype "bidirectional"))
      (node (ref "U$2") (pin "8") (pinfunction "VDD_8") (pintype "bidirectional"))
      (node (ref "U$7") (pin "4") (pinfunction "VDD_4") (pintype "power_in"))
      (node (ref "U1") (pin "4") (pinfunction "VCC_4") (pintype "bidirectional"))
      (node (ref "U3") (pin "14") (pinfunction "IOVDD_14") (pintype "power_in"))
      (node (ref "U3") (pin "19") (pinfunction "IOVDD_19") (pintype "power_in"))
      (node (ref "U3") (pin "32") (pinfunction "TEST_32") (pintype "input"))
      (node (ref "U3") (pin "6") (pinfunction "IOVDD_6") (pintype "power_in"))
    )
    (net (code "3") (name "AN_3V") (class "Default")
      (node (ref "C9") (pin "1") (pinfunction "1_1") (pintype "passive"))
      (node (ref "IC3") (pin "30") (pinfunction "AVDD_30") (pintype "bidirectional"))
      (node (ref "R18") (pin "2") (pinfunction "2_2") (pintype "passive"))
    )
    (net (code "4") (name "DP_RST") (class "Default")
      (node (ref "IC3") (pin "34") (pinfunction "RB10/AN10/CVREF/PMA13_34") (pintype "bidirectional"))
      (node (ref "IC4") (pin "29") (pinfunction "RESET_N_29") (pintype "input"))
      (node (ref "R1") (pin "2") (pinfunction "2_2") (pintype "passive"))
    )
    (net (code "5") (name "D_N") (class "Default")
      (node (ref "IC1") (pin "6") (pinfunction "I/O1_6") (pintype "bidirectional"))
      (node (ref "IC3") (pin "56") (pinfunction "D-/RG3_56") (pintype "bidirectional"))
    )
    (net (code "6") (name "D_P") (class "Default")
      (node (ref "IC1") (pin "4") (pinfunction "I/O2_4") (pintype "bidirectional"))
      (node (ref "IC3") (pin "57") (pinfunction "D+/RG2_57") (pintype "bidirectional"))
    )
    (net (code "7") (name "ECRSDV") (class "Default")
      (node (ref "IC3") (pin "12") (pinfunction "ERXDV/SCL2A/U2ATX/PMA3/CN10/SDO2A/RG8_12") (pintype "bidirectional"))
      (node (ref "IC4") (pin "40") (pinfunction "CRS_40") (pintype "bidirectional"))
    )
    (net (code "8") (name "EINT") (class "Default")
      (node (ref "IC4") (pin "7") (pinfunction "PWRDN_INTN_7") (pintype "bidirectional"))
      (node (ref "R19") (pin "1") (pinfunction "1_1") (pintype "passive"))
    )
    (net (code "9") (name "EMDC") (class "Default")
      (node (ref "IC3") (pin "71") (pinfunction "EMDC/IC4/PMCS1/PMA14/RD11_71") (pintype "bidirectional"))
      (node (ref "IC4") (pin "31") (pinfunction "MDC_31") (pintype "input"))
    )
    (net (code "10") (name "EMDIO") (class "Default")
      (node (ref "IC3") (pin "68") (pinfunction "EMDIO/IC1/RTCC/RD8_68") (pintype "bidirectional"))
      (node (ref "IC4") (pin "30") (pinfunction "MDIO_30") (pintype "bidirectional"))
      (node (ref "R15") (pin "2") (pinfunction "2_2") (pintype "passive"))
    )
    (net (code "11") (name "EREFCLK") (class "Default")
      (node (ref "IC3") (pin "14") (pinfunction "ERXCLK/SS2A/U2BRX/U2ACTS/PMA2/CN11/RG9_14") (pintype "bidirectional"))
      (node (ref "IC4") (pin "34") (pinfunction "X1_34") (pintype "input"))
      (node (ref "U$7") (pin "3") (pinfunction "OUT_3") (pintype "output"))
    )
    (net (code "12") (name "ERXD0") (class "Default")
      (node (ref "IC3") (pin "41") (pinfunction "RB12/AN12/PMA11/ERXD0/AECRS_41") (pintype "bidirectional"))
      (node (ref "IC4") (pin "43") (pinfunction "RXD_0_43") (pintype "bidirectional"))
    )
    (net (code "13") (name "ERXD1") (class "Default")
      (node (ref "IC3") (pin "42") (pinfunction "RB13/AN13/PMA10/ERXD1/AECOL_42") (pintype "bidirectional"))
      (node (ref "IC4") (pin "44") (pinfunction "RXD_1_44") (pintype "bidirectional"))
    )
    (net (code "14") (name "ERXERR") (class "Default")
      (node (ref "IC3") (pin "35") (pinfunction "RB11/AN11/PMA12/ERXERR/AETXERR_35") (pintype "bidirectional"))
      (node (ref "IC4") (pin "41") (pinfunction "RX_ER_41") (pintype "bidirectional"))
    )
    (net (code "15") (name "ETXD0") (class "Default")
      (node (ref "IC3") (pin "88") (pinfunction "C1TX/ETXD0/PMD10/RF1_88") (pintype "bidirectional"))
      (node (ref "IC4") (pin "3") (pinfunction "TXD_0_3") (pintype "bidirectional"))
    )
    (net (code "16") (name "ETXD1") (class "Default")
      (node (ref "IC3") (pin "87") (pinfunction "C1RX/ETXD1/PMD11/RF0_87") (pintype "bidirectional"))
      (node (ref "IC4") (pin "4") (pinfunction "TXD_1_4") (pintype "bidirectional"))
    )
    (net (code "17") (name "ETXEN") (class "Default")
      (node (ref "IC3") (pin "83") (pinfunction "ETXEN/CN15/PMD14/RD6_83") (pintype "bidirectional"))
      (node (ref "IC4") (pin "2") (pinfunction "TX_EN_2") (pintype "bidirectional"))
    )
    (net (code "18") (name "FLASH_CS") (class "Default")
      (node (ref "IC3") (pin "38") (pinfunction "RA1/TCK_38") (pintype "bidirectional"))
      (node (ref "R13") (pin "1") (pinfunction "1_1") (pintype "passive"))
      (node (ref "U$2") (pin "1") (pinfunction "~{CE}_1") (pintype "bidirectional"))
    )
    (net (code "19") (name "GND") (class "Default")
      (node (ref "C1") (pin "2") (pinfunction "2_2") (pintype "passive"))
      (node (ref "C10") (pin "2") (pinfunction "2_2") (pintype "passive"))
      (node (ref "C11") (pin "2") (pinfunction "2_2") (pintype "passive"))
      (node (ref "C12") (pin "-") (pinfunction "-_-") (pintype "passive"))
      (node (ref "C13") (pin "2") (pinfunction "2_2") (pintype "passive"))
      (node (ref "C14") (pin "2") (pinfunction "2_2") (pintype "passive"))
      (node (ref "C15") (pin "-") (pinfunction "-_-") (pintype "passive"))
      (node (ref "C16") (pin "2") (pinfunction "2_2") (pintype "passive"))
      (node (ref "C17") (pin "2") (pinfunction "2_2") (pintype "passive"))
      (node (ref "C18") (pin "2") (pinfunction "2_2") (pintype "passive"))
      (node (ref "C19") (pin "2") (pinfunction "2_2") (pintype "passive"))
      (node (ref "C2") (pin "2") (pinfunction "2_2") (pintype "passive"))
      (node (ref "C20") (pin "1") (pinfunction "1_1") (pintype "passive"))
      (node (ref "C21") (pin "2") (pinfunction "2_2") (pintype "passive"))
      (node (ref "C22") (pin "2") (pinfunction "2_2") (pintype "passive"))
      (node (ref "C23") (pin "1") (pinfunction "1_1") (pintype "passive"))
      (node (ref "C24") (pin "2") (pinfunction "2_2") (pintype "passive"))
      (node (ref "C25") (pin "2") (pinfunction "2_2") (pintype "passive"))
      (node (ref "C26") (pin "-") (pinfunction "-_-") (pintype "passive"))
      (node (ref "C27") (pin "2") (pinfunction "2_2") (pintype "passive"))
      (node (ref "C28") (pin "2") (pinfunction "2_2") (pintype "passive"))
      (node (ref "C29") (pin "2") (pinfunction "2_2") (pintype "passive"))
      (node (ref "C3") (pin "2") (pinfunction "2_2") (pintype "passive"))
      (node (ref "C30") (pin "-") (pinfunction "-_-") (pintype "passive"))
      (node (ref "C31") (pin "2") (pinfunction "2_2") (pintype "passive"))
      (node (ref "C32") (pin "2") (pinfunction "2_2") (pintype "passive"))
      (node (ref "C38") (pin "2") (pinfunction "2_2") (pintype "passive"))
      (node (ref "C4") (pin "2") (pinfunction "2_2") (pintype "passive"))
      (node (ref "C40") (pin "2") (pinfunction "2_2") (pintype "passive"))
      (node (ref "C41") (pin "2") (pinfunction "2_2") (pintype "passive"))
      (node (ref "C42") (pin "2") (pinfunction "2_2") (pintype "passive"))
      (node (ref "C45") (pin "2") (pinfunction "2_2") (pintype "passive"))
      (node (ref "C46") (pin "2") (pinfunction "2_2") (pintype "passive"))
      (node (ref "C47") (pin "2") (pinfunction "2_2") (pintype "passive"))
      (node (ref "C48") (pin "2") (pinfunction "2_2") (pintype "passive"))
      (node (ref "C49") (pin "2") (pinfunction "2_2") (pintype "passive"))
      (node (ref "C5") (pin "-") (pinfunction "-_-") (pintype "passive"))
      (node (ref "C50") (pin "2") (pinfunction "2_2") (pintype "passive"))
      (node (ref "C51") (pin "-") (pinfunction "-_-") (pintype "passive"))
      (node (ref "C52") (pin "-") (pinfunction "-_-") (pintype "passive"))
      (node (ref "C53") (pin "2") (pinfunction "2_2") (pintype "passive"))
      (node (ref "C54") (pin "2") (pinfunction "2_2") (pintype "passive"))
      (node (ref "C55") (pin "2") (pinfunction "2_2") (pintype "passive"))
      (node (ref "C56") (pin "2") (pinfunction "2_2") (pintype "passive"))
      (node (ref "C57") (pin "2") (pinfunction "2_2") (pintype "passive"))
      (node (ref "C59") (pin "2") (pinfunction "2_2") (pintype "passive"))
      (node (ref "C6") (pin "2") (pinfunction "2_2") (pintype "passive"))
      (node (ref "C7") (pin "2") (pinfunction "2_2") (pintype "passive"))
      (node (ref "C8") (pin "2") (pinfunction "2_2") (pintype "passive"))
      (node (ref "C9") (pin "2") (pinfunction "2_2") (pintype "passive"))
      (node (ref "IC1") (pin "2") (pinfunction "GND_2") (pintype "bidirectional"))
      (node (ref "IC2") (pin "1") (pinfunction "GND_1") (pintype "input"))
      (node (ref "IC3") (pin "15") (pinfunction "VSS_15") (pintype "power_in"))
      (node (ref "IC3") (pin "31") (pinfunction "AVSS_31") (pintype "bidirectional"))
      (node (ref "IC3") (pin "36") (pinfunction "VSS_36") (pintype "power_in"))
      (node (ref "IC3") (pin "45") (pinfunction "VSS_45") (pintype "power_in"))
      (node (ref "IC3") (pin "65") (pinfunction "VSS_65") (pintype "power_in"))
      (node (ref "IC3") (pin "75") (pinfunction "VSS_75") (pintype "power_in"))
      (node (ref "IC4") (pin "15") (pinfunction "CDVSS_15") (pintype "power_in"))
      (node (ref "IC4") (pin "19") (pinfunction "ANA18VSS_19") (pintype "power_in"))
      (node (ref "IC4") (pin "35") (pinfunction "IO_VSS2_35") (pintype "power_in"))
      (node (ref "IC4") (pin "36") (pinfunction "CORE_VSS_36") (pintype "power_in"))
      (node (ref "IC4") (pin "47") (pinfunction "IO_VSS1_47") (pintype "power_in"))
      (node (ref "IC4") (pin "6") (pinfunction "TXD_3_6") (pintype "bidirectional"))
      (node (ref "IC5") (pin "1") (pinfunction "GND_1") (pintype "input"))
      (node (ref "JP2") (pin "3") (pinfunction "3_3") (pintype "passive"))
      (node (ref "JP3") (pin "1") (pinfunction "1_1") (pintype "passive"))
      (node (ref "JP5") (pin "GND1") (pinfunction "GND_GND1") (pintype "bidirectional"))
      (node (ref "R17") (pin "2") (pinfunction "2_2") (pintype "passive"))
      (node (ref "R21") (pin "1") (pinfunction "1_1") (pintype "passive"))
      (node (ref "R26") (pin "2") (pinfunction "2_2") (pintype "passive"))
      (node (ref "R27") (pin "2") (pinfunction "2_2") (pintype "passive"))
      (node (ref "R28") (pin "2") (pinfunction "2_2") (pintype "passive"))
      (node (ref "R29") (pin "2") (pinfunction "2_2") (pintype "passive"))
      (node (ref "R36") (pin "2") (pinfunction "2_2") (pintype "passive"))
      (node (ref "R6") (pin "2") (pinfunction "2_2") (pintype "passive"))
      (node (ref "RJ1") (pin "GND") (pinfunction "GND_GND") (pintype "bidirectional"))
      (node (ref "RJ1") (pin "SHIELD0") (pinfunction "SHIELD0_SHIELD0") (pintype "bidirectional"))
      (node (ref "RJ1") (pin "SHIELD1") (pinfunction "SHIELD1_SHIELD1") (pintype "bidirectional"))
      (node (ref "SV1") (pin "29") (pinfunction "29_29") (pintype "passive"))
      (node (ref "SV1") (pin "30") (pinfunction "30_30") (pintype "passive"))
      (node (ref "U$1") (pin "2") (pinfunction "GND_2") (pintype "power_in"))
      (node (ref "U$2") (pin "4") (pinfunction "VSS_4") (pintype "bidirectional"))
      (node (ref "U$7") (pin "2") (pinfunction "GND_2") (pintype "power_in"))
      (node (ref "U1") (pin "6") (pinfunction "GND_6") (pintype "bidirectional"))
      (node (ref "U1") (pin "CD2") (pinfunction "SHIELD_CD2") (pintype "bidirectional"))
      (node (ref "U1") (pin "GND1") (pinfunction "SHIELD_GND1") (pintype "bidirectional"))
      (node (ref "U1") (pin "GND2") (pinfunction "SHIELD_GND2") (pintype "bidirectional"))
      (node (ref "U3") (pin "16") (pinfunction "DGND_16") (pintype "power_in"))
      (node (ref "U3") (pin "20") (pinfunction "DGND_20") (pintype "power_in"))
      (node (ref "U3") (pin "21") (pinfunction "DGND_21") (pintype "power_in"))
      (node (ref "U3") (pin "22") (pinfunction "DGND_22") (pintype "power_in"))
      (node (ref "U3") (pin "35") (pinfunction "DGND_35") (pintype "power_in"))
      (node (ref "U3") (pin "4") (pinfunction "DGND_4") (pintype "power_in"))
      (node (ref "X1") (pin "2") (pinfunction "S_2") (pintype "passive"))
      (node (ref "X3") (pin "4") (pinfunction "4_4") (pintype "passive"))
      (node (ref "X3") (pin "M1") (pinfunction "S1_M1") (pintype "passive"))
      (node (ref "X3") (pin "M2") (pinfunction "S2_M2") (pintype "passive"))
      (node (ref "Y3") (pin "2") (pinfunction "3_2") (pintype "passive"))
      (node (ref "Y3") (pin "4") (pinfunction "3_4") (pintype "passive"))
    )
    (net (code "20") (name "LED_ACT") (class "Default")
      (node (ref "IC4") (pin "26") (pinfunction "LED_ACTCOL_26") (pintype "bidirectional"))
      (node (ref "RJ1") (pin "G-") (pinfunction "G-_G-") (pintype "bidirectional"))
    )
    (net (code "21") (name "LED_LINK") (class "Default")
      (node (ref "IC4") (pin "28") (pinfunction "LED_LNK_28") (pintype "bidirectional"))
      (node (ref "RJ1") (pin "Y-") (pinfunction "Y-_Y-") (pintype "bidirectional"))
    )
    (net (code "22") (name "MCLR") (class "Default")
      (node (ref "C28") (pin "1") (pinfunction "1_1") (pintype "passive"))
      (node (ref "IC3") (pin "13") (pinfunction "MCLR_13") (pintype "bidirectional"))
      (node (ref "JP2") (pin "1") (pinfunction "1_1") (pintype "passive"))
      (node (ref "R9") (pin "1") (pinfunction "1_1") (pintype "passive"))
    )
    (net (code "23") (name "MISO") (class "Default")
      (node (ref "IC3") (pin "49") (pinfunction "SDA3A/SDI3A/U3ARX/PMA9/CN17/RF4_49") (pintype "bidirectional"))
      (node (ref "R16") (pin "1") (pinfunction "1_1") (pintype "passive"))
      (node (ref "U$2") (pin "2") (pinfunction "SO_2") (pintype "bidirectional"))
      (node (ref "U1") (pin "7") (pinfunction "DO_7") (pintype "bidirectional"))
    )
    (net (code "24") (name "MOSI") (class "Default")
      (node (ref "IC3") (pin "50") (pinfunction "SCL3A/SDO3A/U3ATX/PMA8/CN18/RF5_50") (pintype "bidirectional"))
      (node (ref "U$2") (pin "5") (pinfunction "SI_5") (pintype "bidirectional"))
      (node (ref "U1") (pin "3") (pinfunction "DI_3") (pintype "bidirectional"))
    )
    (net (code "25") (name "Net-(C36-Pad2)") (class "Default")
      (node (ref "C36") (pin "2") (pinfunction "2_2") (pintype "passive"))
      (node (ref "R23") (pin "1") (pinfunction "1_1") (pintype "passive"))
    )
    (net (code "26") (name "Net-(C37-Pad2)") (class "Default")
      (node (ref "C37") (pin "2") (pinfunction "2_2") (pintype "passive"))
      (node (ref "R24") (pin "1") (pinfunction "1_1") (pintype "passive"))
    )
    (net (code "27") (name "Net-(C39-Pad2)") (class "Default")
      (node (ref "C39") (pin "2") (pinfunction "2_2") (pintype "passive"))
      (node (ref "R22") (pin "1") (pinfunction "1_1") (pintype "passive"))
    )
    (net (code "28") (name "Net-(C43-Pad1)") (class "Default")
      (node (ref "C43") (pin "1") (pinfunction "1_1") (pintype "passive"))
      (node (ref "R31") (pin "1") (pinfunction "1_1") (pintype "passive"))
    )
    (net (code "29") (name "Net-(C43-Pad2)") (class "Default")
      (node (ref "C43") (pin "2") (pinfunction "2_2") (pintype "passive"))
      (node (ref "J1") (pin "TIP") (pinfunction "TIP_TIP") (pintype "bidirectional"))
      (node (ref "R34") (pin "1") (pinfunction "1_1") (pintype "passive"))
    )
    (net (code "30") (name "Net-(C44-Pad1)") (class "Default")
      (node (ref "C44") (pin "1") (pinfunction "1_1") (pintype "passive"))
      (node (ref "R32") (pin "1") (pinfunction "1_1") (pintype "passive"))
    )
    (net (code "31") (name "Net-(C44-Pad2)") (class "Default")
      (node (ref "C44") (pin "2") (pinfunction "2_2") (pintype "passive"))
      (node (ref "J1") (pin "RING1") (pinfunction "RING1_RING1") (pintype "bidirectional"))
      (node (ref "R33") (pin "1") (pinfunction "1_1") (pintype "passive"))
    )
    (net (code "32") (name "Net-(C63-Pad1)") (class "Default")
      (node (ref "C63") (pin "1") (pinfunction "1_1") (pintype "passive"))
      (node (ref "R12") (pin "1") (pinfunction "1_1") (pintype "passive"))
    )
    (net (code "33") (name "Net-(C63-Pad2)") (class "Default")
      (node (ref "C63") (pin "2") (pinfunction "2_2") (pintype "passive"))
      (node (ref "JP1") (pin "2") (pinfunction "2_2") (pintype "passive"))
    )
    (net (code "34") (name "Net-(C64-Pad1)") (class "Default")
      (node (ref "C64") (pin "1") (pinfunction "1_1") (pintype "passive"))
      (node (ref "R37") (pin "1") (pinfunction "1_1") (pintype "passive"))
    )
    (net (code "35") (name "Net-(C64-Pad2)") (class "Default")
      (node (ref "C64") (pin "2") (pinfunction "2_2") (pintype "passive"))
      (node (ref "JP1") (pin "1") (pinfunction "1_1") (pintype "passive"))
    )
    (net (code "36") (name "Net-(IC1-I{slash}O_1)") (class "Default")
      (node (ref "IC1") (pin "1") (pinfunction "I/O_1_1") (pintype "bidirectional"))
      (node (ref "X3") (pin "2") (pinfunction "2_2") (pintype "passive"))
    )
    (net (code "37") (name "Net-(IC1-I{slash}O_2)") (class "Default")
      (node (ref "IC1") (pin "3") (pinfunction "I/O_2_3") (pintype "bidirectional"))
      (node (ref "X3") (pin "3") (pinfunction "3_3") (pintype "passive"))
    )
    (net (code "38") (name "Net-(IC3-OSC1{slash}CLKI{slash}RC12)") (class "Default")
      (node (ref "IC3") (pin "63") (pinfunction "OSC1/CLKI/RC12_63") (pintype "bidirectional"))
      (node (ref "U$1") (pin "3") (pinfunction "OUT_3") (pintype "output"))
    )
    (net (code "39") (name "Net-(IC3-RC13{slash}CN1{slash}SOSCI)") (class "Default")
      (node (ref "C20") (pin "2") (pinfunction "2_2") (pintype "passive"))
      (node (ref "IC3") (pin "73") (pinfunction "RC13/CN1/SOSCI_73") (pintype "bidirectional"))
      (node (ref "X2") (pin "1") (pinfunction "1_1") (pintype "passive"))
    )
    (net (code "40") (name "Net-(IC3-RC14{slash}CN0{slash}SOSCO{slash}T1CK)") (class "Default")
      (node (ref "C23") (pin "2") (pinfunction "2_2") (pintype "passive"))
      (node (ref "IC3") (pin "74") (pinfunction "RC14/CN0/SOSCO/T1CK_74") (pintype "bidirectional"))
      (node (ref "X2") (pin "2") (pinfunction "2_2") (pintype "passive"))
    )
    (net (code "41") (name "Net-(IC3-VDDCORE)") (class "Default")
      (node (ref "C10") (pin "1") (pinfunction "1_1") (pintype "passive"))
      (node (ref "IC3") (pin "85") (pinfunction "VDDCORE_85") (pintype "bidirectional"))
    )
    (net (code "42") (name "Net-(IC4-IP_PH_M)") (class "Default")
      (node (ref "IC4") (pin "20") (pinfunction "IP_PH_M_20") (pintype "input"))
      (node (ref "R10") (pin "1") (pinfunction "1_1") (pintype "passive"))
    )
    (net (code "43") (name "Net-(IC4-IP_PH_P)") (class "Default")
      (node (ref "IC4") (pin "21") (pinfunction "IP_PH_P_21") (pintype "input"))
      (node (ref "R7") (pin "1") (pinfunction "1_1") (pintype "passive"))
    )
    (net (code "44") (name "Net-(IC4-RX_DV)") (class "Default")
      (node (ref "IC4") (pin "39") (pinfunction "RX_DV_39") (pintype "bidirectional"))
      (node (ref "R20") (pin "2") (pinfunction "2_2") (pintype "passive"))
    )
    (net (code "45") (name "Net-(IC4-VREF)") (class "Default")
      (node (ref "IC4") (pin "24") (pinfunction "VREF_24") (pintype "bidirectional"))
      (node (ref "R6") (pin "1") (pinfunction "1_1") (pintype "passive"))
    )
    (net (code "46") (name "Net-(JP5-VCC)") (class "Default")
      (node (ref "F1") (pin "1") (pinfunction "1_1") (pintype "passive"))
      (node (ref "JP5") (pin "VBUS1") (pinfunction "VCC_VBUS1") (pintype "bidirectional"))
      (node (ref "X1") (pin "1") (pinfunction "S_1") (pintype "passive"))
    )
    (net (code "47") (name "Net-(R42-Pad2)") (class "Default")
      (node (ref "R42") (pin "2") (pinfunction "2_2") (pintype "passive"))
      (node (ref "RJ1") (pin "G+") (pinfunction "G+_G+") (pintype "bidirectional"))
    )
    (net (code "48") (name "Net-(R43-Pad1)") (class "Default")
      (node (ref "R43") (pin "1") (pinfunction "1_1") (pintype "passive"))
      (node (ref "RJ1") (pin "Y+") (pinfunction "Y+_Y+") (pintype "bidirectional"))
    )
    (net (code "49") (name "Net-(U3A-GBUF)") (class "Default")
      (node (ref "R23") (pin "2") (pinfunction "2_2") (pintype "passive"))
      (node (ref "U3") (pin "42") (pinfunction "GBUF_42") (pintype "output"))
    )
    (net (code "50") (name "Net-(U3A-GPIO0)") (class "Default")
      (node (ref "R26") (pin "1") (pinfunction "1_1") (pintype "passive"))
      (node (ref "U3") (pin "33") (pinfunction "GPIO0_33") (pintype "bidirectional"))
    )
    (net (code "51") (name "Net-(U3A-GPIO1)") (class "Default")
      (node (ref "R27") (pin "1") (pinfunction "1_1") (pintype "passive"))
      (node (ref "U3") (pin "34") (pinfunction "GPIO1_34") (pintype "bidirectional"))
      (node (ref "U3") (pin "36") (pinfunction "GPIO4/I2S_LROUT_36") (pintype "bidirectional"))
    )
    (net (code "52") (name "Net-(U3A-GPIO2{slash}DCLK)") (class "Default")
      (node (ref "R28") (pin "1") (pinfunction "1_1") (pintype "passive"))
      (node (ref "U3") (pin "9") (pinfunction "GPIO2/DCLK_9") (pintype "bidirectional"))
    )
    (net (code "53") (name "Net-(U3A-GPIO3{slash}SDATA)") (class "Default")
      (node (ref "R29") (pin "1") (pinfunction "1_1") (pintype "passive"))
      (node (ref "U3") (pin "10") (pinfunction "GPIO3/SDATA_10") (pintype "bidirectional"))
      (node (ref "U3") (pin "11") (pinfunction "GPIO6/I2S_SCLK_11") (pintype "bidirectional"))
      (node (ref "U3") (pin "12") (pinfunction "GPIO7/I2S_DATA_12") (pintype "bidirectional"))
    )
    (net (code "54") (name "Net-(U3A-GPIO5{slash}I2S_MCLK)") (class "Default")
      (node (ref "R17") (pin "1") (pinfunction "1_1") (pintype "passive"))
      (node (ref "U3") (pin "25") (pinfunction "GPIO5/I2S_MCLK_25") (pintype "bidirectional"))
    )
    (net (code "55") (name "Net-(U3A-LEFT)") (class "Default")
      (node (ref "R22") (pin "2") (pinfunction "2_2") (pintype "passive"))
      (node (ref "R31") (pin "2") (pinfunction "2_2") (pintype "passive"))
      (node (ref "U3") (pin "46") (pinfunction "LEFT_46") (pintype "output"))
    )
    (net (code "56") (name "Net-(U3A-LINEINR)") (class "Default")
      (node (ref "C61") (pin "2") (pinfunction "2_2") (pintype "passive"))
      (node (ref "R37") (pin "2") (pinfunction "2_2") (pintype "passive"))
      (node (ref "U3") (pin "48") (pinfunction "LINEINR_48") (pintype "input"))
    )
    (net (code "57") (name "Net-(U3A-MICP{slash}LINEINL)") (class "Default")
      (node (ref "C62") (pin "2") (pinfunction "2_2") (pintype "passive"))
      (node (ref "R12") (pin "2") (pinfunction "2_2") (pintype "passive"))
      (node (ref "U3") (pin "1") (pinfunction "MICP/LINEINL_1") (pintype "input"))
    )
    (net (code "58") (name "Net-(U3A-RCAP)") (class "Default")
      (node (ref "R25") (pin "2") (pinfunction "2_2") (pintype "passive"))
      (node (ref "U3") (pin "44") (pinfunction "RCAP_44") (pintype "bidirectional"))
    )
    (net (code "59") (name "Net-(U3A-RIGHT)") (class "Default")
      (node (ref "R24") (pin "2") (pinfunction "2_2") (pintype "passive"))
      (node (ref "R32") (pin "2") (pinfunction "2_2") (pintype "passive"))
      (node (ref "U3") (pin "39") (pinfunction "RIGHT_39") (pintype "output"))
    )
    (net (code "60") (name "Net-(U3A-RX)") (class "Default")
      (node (ref "R30") (pin "1") (pinfunction "1_1") (pintype "passive"))
      (node (ref "U3") (pin "26") (pinfunction "RX_26") (pintype "input"))
    )
    (net (code "61") (name "Net-(U3A-XTALI)") (class "Default")
      (node (ref "C50") (pin "1") (pinfunction "1_1") (pintype "passive"))
      (node (ref "R35") (pin "2") (pinfunction "2_2") (pintype "passive"))
      (node (ref "U3") (pin "18") (pinfunction "XTALI_18") (pintype "input"))
      (node (ref "Y3") (pin "1") (pinfunction "2_1") (pintype "passive"))
    )
    (net (code "62") (name "Net-(U3A-XTALO)") (class "Default")
      (node (ref "C49") (pin "1") (pinfunction "1_1") (pintype "passive"))
      (node (ref "R35") (pin "1") (pinfunction "1_1") (pintype "passive"))
      (node (ref "U3") (pin "17") (pinfunction "XTALO_17") (pintype "output"))
      (node (ref "Y3") (pin "3") (pinfunction "1_3") (pintype "passive"))
    )
    (net (code "63") (name "PGEC") (class "Default")
      (node (ref "IC3") (pin "24") (pinfunction "RB1/AN1/CN3/PGC1_24") (pintype "bidirectional"))
      (node (ref "JP2") (pin "5") (pinfunction "5_5") (pintype "passive"))
    )
    (net (code "64") (name "PGED") (class "Default")
      (node (ref "IC3") (pin "25") (pinfunction "RB0/AN0/CN2/PGD1_25") (pintype "bidirectional"))
      (node (ref "JP2") (pin "4") (pinfunction "4_4") (pintype "passive"))
    )
    (net (code "65") (name "RA6") (class "Default")
      (node (ref "IC3") (pin "91") (pinfunction "RA6/TRCLK_91") (pintype "bidirectional"))
      (node (ref "SV1") (pin "17") (pinfunction "17_17") (pintype "passive"))
    )
    (net (code "66") (name "RA7") (class "Default")
      (node (ref "IC3") (pin "92") (pinfunction "RA7/TRD3_92") (pintype "bidirectional"))
      (node (ref "SV1") (pin "20") (pinfunction "20_20") (pintype "passive"))
    )
    (net (code "67") (name "RC3") (class "Default")
      (node (ref "IC3") (pin "8") (pinfunction "RC3/T4CK/AC2RX_8") (pintype "bidirectional"))
    )
    (net (code "68") (name "RC15") (class "Default")
      (node (ref "IC3") (pin "64") (pinfunction "OSC2/CLKO/RC15_64") (pintype "bidirectional"))
      (node (ref "SV1") (pin "4") (pinfunction "4_4") (pintype "passive"))
    )
    (net (code "69") (name "RD1") (class "Default")
      (node (ref "IC3") (pin "76") (pinfunction "OC2/RD1_76") (pintype "bidirectional"))
      (node (ref "SV1") (pin "7") (pinfunction "7_7") (pintype "passive"))
    )
    (net (code "70") (name "RD2") (class "Default")
      (node (ref "IC3") (pin "77") (pinfunction "OC3/RD2_77") (pintype "bidirectional"))
      (node (ref "SV1") (pin "10") (pinfunction "10_10") (pintype "passive"))
    )
    (net (code "71") (name "RD3") (class "Default")
      (node (ref "IC3") (pin "78") (pinfunction "OC4/RD3_78") (pintype "bidirectional"))
      (node (ref "SV1") (pin "9") (pinfunction "9_9") (pintype "passive"))
    )
    (net (code "72") (name "RD4") (class "Default")
      (node (ref "IC3") (pin "81") (pinfunction "PMWR/CN13/OC5/RD4_81") (pintype "bidirectional"))
      (node (ref "SV1") (pin "14") (pinfunction "14_14") (pintype "passive"))
    )
    (net (code "73") (name "RD5") (class "Default")
      (node (ref "IC3") (pin "82") (pinfunction "CN14/PMRD/RD5_82") (pintype "bidirectional"))
      (node (ref "SV1") (pin "13") (pinfunction "13_13") (pintype "passive"))
    )
    (net (code "74") (name "RD7") (class "Default")
      (node (ref "IC3") (pin "84") (pinfunction "ETXCLK/CN16/PMD15/RD7_84") (pintype "bidirectional"))
      (node (ref "SV1") (pin "16") (pinfunction "16_16") (pintype "passive"))
    )
    (net (code "75") (name "RD9") (class "Default")
      (node (ref "IC3") (pin "69") (pinfunction "SS1/IC2/RD9_69") (pintype "bidirectional"))
      (node (ref "SV1") (pin "5") (pinfunction "5_5") (pintype "passive"))
    )
    (net (code "76") (name "RD12") (class "Default")
      (node (ref "IC3") (pin "79") (pinfunction "ETXD2/IC5/PMD12/RD12_79") (pintype "bidirectional"))
      (node (ref "SV1") (pin "12") (pinfunction "12_12") (pintype "passive"))
    )
    (net (code "77") (name "RD13") (class "Default")
      (node (ref "IC3") (pin "80") (pinfunction "ETXD3/CN19/PMD13/RD13_80") (pintype "bidirectional"))
      (node (ref "SV1") (pin "11") (pinfunction "11_11") (pintype "passive"))
    )
    (net (code "78") (name "RD_N") (class "Default")
      (node (ref "IC4") (pin "13") (pinfunction "TPRDM_13") (pintype "bidirectional"))
      (node (ref "R5") (pin "1") (pinfunction "1_1") (pintype "passive"))
      (node (ref "RJ1") (pin "RD-") (pinfunction "RD-_RD-") (pintype "bidirectional"))
    )
    (net (code "79") (name "RD_P") (class "Default")
      (node (ref "IC4") (pin "14") (pinfunction "TPRDP_14") (pintype "bidirectional"))
      (node (ref "R4") (pin "1") (pinfunction "1_1") (pintype "passive"))
      (node (ref "RJ1") (pin "RD+") (pinfunction "RD+_RD+") (pintype "bidirectional"))
    )
    (net (code "80") (name "RE0") (class "Default")
      (node (ref "IC3") (pin "93") (pinfunction "RE0/PMD0_93") (pintype "bidirectional"))
      (node (ref "SV1") (pin "19") (pinfunction "19_19") (pintype "passive"))
    )
    (net (code "81") (name "RE1") (class "Default")
      (node (ref "IC3") (pin "94") (pinfunction "RE1/PMD1_94") (pintype "bidirectional"))
      (node (ref "SV1") (pin "22") (pinfunction "22_22") (pintype "passive"))
    )
    (net (code "82") (name "RE2") (class "Default")
      (node (ref "IC3") (pin "98") (pinfunction "RE2/PMD2_98") (pintype "bidirectional"))
      (node (ref "SV1") (pin "26") (pinfunction "26_26") (pintype "passive"))
    )
    (net (code "83") (name "RE3") (class "Default")
      (node (ref "IC3") (pin "99") (pinfunction "RE3/PMD3_99") (pintype "bidirectional"))
      (node (ref "SV1") (pin "25") (pinfunction "25_25") (pintype "passive"))
    )
    (net (code "84") (name "RE4") (class "Default")
      (node (ref "IC3") (pin "100") (pinfunction "RE4/PMD4_100") (pintype "bidirectional"))
      (node (ref "SV1") (pin "28") (pinfunction "28_28") (pintype "passive"))
    )
    (net (code "85") (name "RE5") (class "Default")
      (node (ref "IC3") (pin "3") (pinfunction "RE5/PMD5_3") (pintype "bidirectional"))
      (node (ref "SV1") (pin "27") (pinfunction "27_27") (pintype "passive"))
    )
    (net (code "86") (name "REG_OUT") (class "Default")
      (node (ref "C18") (pin "1") (pinfunction "1_1") (pintype "passive"))
      (node (ref "C19") (pin "1") (pinfunction "1_1") (pintype "passive"))
      (node (ref "C24") (pin "1") (pinfunction "1_1") (pintype "passive"))
      (node (ref "C32") (pin "1") (pinfunction "1_1") (pintype "passive"))
      (node (ref "IC4") (pin "18") (pinfunction "ANA18VDD_18") (pintype "power_in"))
      (node (ref "IC4") (pin "23") (pinfunction "REG_OUT_23") (pintype "output"))
      (node (ref "IC4") (pin "37") (pinfunction "CORE_VDD_37") (pintype "power_in"))
    )
    (net (code "87") (name "RF2_ROT_SW") (class "Default")
      (node (ref "IC3") (pin "52") (pinfunction "SDA1A/SDI1A/U1ARX/RF2_52") (pintype "bidirectional"))
      (node (ref "SV1") (pin "2") (pinfunction "2_2") (pintype "passive"))
    )
    (net (code "88") (name "RF8") (class "Default")
      (node (ref "IC3") (pin "53") (pinfunction "SCL1A/SDO1A/U1ATX/RF8_53") (pintype "bidirectional"))
      (node (ref "SV1") (pin "1") (pinfunction "1_1") (pintype "passive"))
    )
    (net (code "89") (name "RG0") (class "Default")
      (node (ref "IC3") (pin "90") (pinfunction "C2RX/PMD8/RG0_90") (pintype "bidirectional"))
      (node (ref "SV1") (pin "18") (pinfunction "18_18") (pintype "passive"))
    )
    (net (code "90") (name "RG1") (class "Default")
      (node (ref "IC3") (pin "89") (pinfunction "C2TX/ETXERR/PMD9/RG1_89") (pintype "bidirectional"))
      (node (ref "SV1") (pin "15") (pinfunction "15_15") (pintype "passive"))
    )
    (net (code "91") (name "RG6") (class "Default")
      (node (ref "IC3") (pin "10") (pinfunction "ECOL/U2BTX/U2ARTS/PMA5/CN8/SCK2/RG6_10") (pintype "bidirectional"))
    )
    (net (code "92") (name "RG7_SDA2A") (class "Default")
      (node (ref "IC3") (pin "11") (pinfunction "ECRS/SDA2A/U2ARX/PMA4/CN9/SDI2A/RG7_11") (pintype "bidirectional"))
    )
    (net (code "93") (name "RG12") (class "Default")
      (node (ref "IC3") (pin "96") (pinfunction "TRD1/RG12_96") (pintype "bidirectional"))
      (node (ref "SV1") (pin "24") (pinfunction "24_24") (pintype "passive"))
    )
    (net (code "94") (name "RG13") (class "Default")
      (node (ref "IC3") (pin "97") (pinfunction "TRD0/RG13_97") (pintype "bidirectional"))
      (node (ref "SV1") (pin "23") (pinfunction "23_23") (pintype "passive"))
    )
    (net (code "95") (name "RG14") (class "Default")
      (node (ref "IC3") (pin "95") (pinfunction "TRD2/RG14_95") (pintype "bidirectional"))
      (node (ref "SV1") (pin "21") (pinfunction "21_21") (pintype "passive"))
    )
    (net (code "96") (name "RG15") (class "Default")
      (node (ref "IC3") (pin "1") (pinfunction "AERXERR/RG15_1") (pintype "bidirectional"))
    )
    (net (code "97") (name "RXD") (class "Default")
      (node (ref "IC3") (pin "47") (pinfunction "AETXD0/SS1A/U1BRX/U1ACTS/CN20/RD14_47") (pintype "bidirectional"))
      (node (ref "JP3") (pin "3") (pinfunction "3_3") (pintype "passive"))
    )
    (net (code "98") (name "SCK") (class "Default")
      (node (ref "IC3") (pin "39") (pinfunction "AC1TX/SCK3A/U3BTX/U3ARTS/RF13_39") (pintype "bidirectional"))
      (node (ref "U$2") (pin "6") (pinfunction "SCK_6") (pintype "bidirectional"))
      (node (ref "U1") (pin "5") (pinfunction "SCK_5") (pintype "bidirectional"))
    )
    (net (code "99") (name "SCL1") (class "Default")
      (node (ref "IC3") (pin "66") (pinfunction "RA14/INT3/SCL1/AETXCLK_66") (pintype "bidirectional"))
      (node (ref "SV1") (pin "3") (pinfunction "3_3") (pintype "passive"))
    )
    (net (code "100") (name "SDA1") (class "Default")
      (node (ref "IC3") (pin "67") (pinfunction "RA15/INT4/SDA1/AETXEN_67") (pintype "bidirectional"))
      (node (ref "SV1") (pin "6") (pinfunction "6_6") (pintype "passive"))
    )
    (net (code "101") (name "SD_CS") (class "Default")
      (node (ref "IC3") (pin "44") (pinfunction "RB15/AN15/CN12/OCFB/_44") (pintype "bidirectional"))
      (node (ref "R11") (pin "1") (pinfunction "1_1") (pintype "passive"))
      (node (ref "U1") (pin "2") (pinfunction "CS_2") (pintype "bidirectional"))
    )
    (net (code "102") (name "SD_PRESENT") (class "Default")
      (node (ref "IC3") (pin "51") (pinfunction "USBID/RF3_51") (pintype "bidirectional"))
      (node (ref "R8") (pin "1") (pinfunction "1_1") (pintype "passive"))
      (node (ref "U1") (pin "CD1") (pinfunction "SHIELD_CD1") (pintype "bidirectional"))
    )
    (net (code "103") (name "TD_N") (class "Default")
      (node (ref "IC4") (pin "16") (pinfunction "TPTDM_16") (pintype "bidirectional"))
      (node (ref "R3") (pin "1") (pinfunction "1_1") (pintype "passive"))
      (node (ref "RJ1") (pin "TD-") (pinfunction "TD-_TD-") (pintype "bidirectional"))
    )
    (net (code "104") (name "TD_P") (class "Default")
      (node (ref "IC4") (pin "17") (pinfunction "TPTDP_17") (pintype "bidirectional"))
      (node (ref "R2") (pin "1") (pinfunction "1_1") (pintype "passive"))
      (node (ref "RJ1") (pin "TD+") (pinfunction "TD+_TD+") (pintype "bidirectional"))
    )
    (net (code "105") (name "TXD") (class "Default")
      (node (ref "IC3") (pin "48") (pinfunction "AETXD1/SCK1A/U1BTX/U1ARTS/CN21/BCLK1/RD15_48") (pintype "bidirectional"))
      (node (ref "JP3") (pin "2") (pinfunction "2_2") (pintype "passive"))
    )
    (net (code "106") (name "VBUS") (class "Default")
      (node (ref "C12") (pin "+") (pinfunction "+_+") (pintype "passive"))
      (node (ref "C13") (pin "1") (pinfunction "1_1") (pintype "passive"))
      (node (ref "C27") (pin "1") (pinfunction "1_1") (pintype "passive"))
      (node (ref "C30") (pin "+") (pinfunction "+_+") (pintype "passive"))
      (node (ref "C5") (pin "+") (pinfunction "+_+") (pintype "passive"))
      (node (ref "C52") (pin "+") (pinfunction "+_+") (pintype "passive"))
      (node (ref "C53") (pin "1") (pinfunction "1_1") (pintype "passive"))
      (node (ref "F1") (pin "2") (pinfunction "2_2") (pintype "passive"))
      (node (ref "IC1") (pin "5") (pinfunction "VBUS_5") (pintype "bidirectional"))
      (node (ref "IC2") (pin "3") (pinfunction "IN_3") (pintype "input"))
      (node (ref "IC3") (pin "54") (pinfunction "VBUS_54") (pintype "bidirectional"))
      (node (ref "IC5") (pin "3") (pinfunction "IN_3") (pintype "input"))
      (node (ref "SV1") (pin "31") (pinfunction "31_31") (pintype "passive"))
      (node (ref "SV1") (pin "32") (pinfunction "32_32") (pintype "passive"))
      (node (ref "X3") (pin "1") (pinfunction "1_1") (pintype "passive"))
    )
    (net (code "107") (name "VS_AGND") (class "Default")
      (node (ref "C33") (pin "2") (pinfunction "2_2") (pintype "passive"))
      (node (ref "C34") (pin "2") (pinfunction "2_2") (pintype "passive"))
      (node (ref "C35") (pin "2") (pinfunction "2_2") (pintype "passive"))
      (node (ref "C36") (pin "1") (pinfunction "1_1") (pintype "passive"))
      (node (ref "C37") (pin "1") (pinfunction "1_1") (pintype "passive"))
      (node (ref "C39") (pin "1") (pinfunction "1_1") (pintype "passive"))
      (node (ref "C58") (pin "2") (pinfunction "2_2") (pintype "passive"))
      (node (ref "C61") (pin "1") (pinfunction "1_1") (pintype "passive"))
      (node (ref "C62") (pin "1") (pinfunction "1_1") (pintype "passive"))
      (node (ref "J1") (pin "EARTH") (pinfunction "EARTH_EARTH") (pintype "bidirectional"))
      (node (ref "JP1") (pin "3") (pinfunction "3_3") (pintype "passive"))
      (node (ref "R21") (pin "2") (pinfunction "2_2") (pintype "passive"))
      (node (ref "R25") (pin "1") (pinfunction "1_1") (pintype "passive"))
      (node (ref "R33") (pin "2") (pinfunction "2_2") (pintype "passive"))
      (node (ref "R34") (pin "2") (pinfunction "2_2") (pintype "passive"))
      (node (ref "U3") (pin "37") (pinfunction "AGND_37") (pintype "power_in"))
      (node (ref "U3") (pin "40") (pinfunction "AGND_40") (pintype "power_in"))
      (node (ref "U3") (pin "41") (pinfunction "AGND_41") (pintype "power_in"))
      (node (ref "U3") (pin "47") (pinfunction "AGND_47") (pintype "power_in"))
    )
    (net (code "108") (name "VS_AVDD") (class "Default")
      (node (ref "C33") (pin "1") (pinfunction "1_1") (pintype "passive"))
      (node (ref "C34") (pin "1") (pinfunction "1_1") (pintype "passive"))
      (node (ref "C35") (pin "1") (pinfunction "1_1") (pintype "passive"))
      (node (ref "C58") (pin "1") (pinfunction "1_1") (pintype "passive"))
      (node (ref "L1") (pin "1") (pinfunction "1_1") (pintype "passive"))
      (node (ref "U3") (pin "38") (pinfunction "AVDD_38") (pintype "power_in"))
      (node (ref "U3") (pin "43") (pinfunction "AVDD_43") (pintype "power_in"))
      (node (ref "U3") (pin "45") (pinfunction "AVDD_45") (pintype "power_in"))
    )
    (net (code "109") (name "VS_CVDD") (class "Default")
      (node (ref "C45") (pin "1") (pinfunction "1_1") (pintype "passive"))
      (node (ref "C46") (pin "1") (pinfunction "1_1") (pintype "passive"))
      (node (ref "C47") (pin "1") (pinfunction "1_1") (pintype "passive"))
      (node (ref "C48") (pin "1") (pinfunction "1_1") (pintype "passive"))
      (node (ref "C57") (pin "1") (pinfunction "1_1") (pintype "passive"))
      (node (ref "L2") (pin "1") (pinfunction "1_1") (pintype "passive"))
      (node (ref "U3") (pin "24") (pinfunction "CVDD_24") (pintype "power_in"))
      (node (ref "U3") (pin "31") (pinfunction "CVDD_31") (pintype "power_in"))
      (node (ref "U3") (pin "5") (pinfunction "CVDD_5") (pintype "power_in"))
      (node (ref "U3") (pin "7") (pinfunction "CVDD_7") (pintype "power_in"))
    )
    (net (code "110") (name "VS_DREQ") (class "Default")
      (node (ref "IC3") (pin "6") (pinfunction "RC1/T2CK_6") (pintype "bidirectional"))
      (node (ref "U3") (pin "8") (pinfunction "DREQ_8") (pintype "output"))
    )
    (net (code "111") (name "VS_MISO") (class "Default")
      (node (ref "IC3") (pin "9") (pinfunction "RC4/T5CK/SDI1_9") (pintype "bidirectional"))
      (node (ref "U3") (pin "30") (pinfunction "SO_30") (pintype "output"))
    )
    (net (code "112") (name "VS_MOSI") (class "Default")
      (node (ref "IC3") (pin "72") (pinfunction "SDO1/INT0/OC1/RD0_72") (pintype "bidirectional"))
      (node (ref "U3") (pin "29") (pinfunction "SI_29") (pintype "input"))
    )
    (net (code "113") (name "VS_SCK") (class "Default")
      (node (ref "IC3") (pin "70") (pinfunction "SCKI/IC3/PMCS2/PMA15/RD10_70") (pintype "bidirectional"))
      (node (ref "U3") (pin "28") (pinfunction "SCLK_28") (pintype "input"))
    )
    (net (code "114") (name "VS_XCS") (class "Default")
      (node (ref "IC3") (pin "5") (pinfunction "RE7/PMD7_5") (pintype "bidirectional"))
      (node (ref "U3") (pin "23") (pinfunction "XCS_23") (pintype "input"))
    )
    (net (code "115") (name "VS_XDCS") (class "Default")
      (node (ref "IC3") (pin "4") (pinfunction "RE6/PMD6_4") (pintype "bidirectional"))
      (node (ref "U3") (pin "13") (pinfunction "XDCS/BSYNC_13") (pintype "input"))
    )
    (net (code "116") (name "VS_XRST") (class "Default")
      (node (ref "IC3") (pin "7") (pinfunction "RC2/T3CK/AC2TX_7") (pintype "bidirectional"))
      (node (ref "R36") (pin "1") (pinfunction "1_1") (pintype "passive"))
      (node (ref "U3") (pin "3") (pinfunction "XRESET_3") (pintype "input"))
    )
    (net (code "117") (name "_1V8") (class "Default")
      (node (ref "C51") (pin "+") (pinfunction "+_+") (pintype "passive"))
      (node (ref "C54") (pin "1") (pinfunction "1_1") (pintype "passive"))
      (node (ref "IC5") (pin "2") (pinfunction "OUT_2") (pintype "passive"))
      (node (ref "IC5") (pin "TAB") (pinfunction "OUT1_TAB") (pintype "passive"))
      (node (ref "L2") (pin "2") (pinfunction "2_2") (pintype "passive"))
    )
    (net (code "118") (name "unconnected-(IC3-AC1RX{slash}SS3A{slash}U3BRX{slash}U3ACTS{slash}RF12-Pad40)") (class "Default")
      (node (ref "IC3") (pin "40") (pinfunction "AC1RX/SS3A/U3BRX/U3ACTS/RF12_40") (pintype "bidirectional"))
    )
    (net (code "119") (name "unconnected-(IC3-RA0{slash}TMS-Pad17)") (class "Default")
      (node (ref "IC3") (pin "17") (pinfunction "RA0/TMS_17") (pintype "bidirectional"))
    )
    (net (code "120") (name "unconnected-(IC3-RA2{slash}SCL2-Pad58)") (class "Default")
      (node (ref "IC3") (pin "58") (pinfunction "RA2/SCL2_58") (pintype "bidirectional"))
    )
    (net (code "121") (name "unconnected-(IC3-RA3{slash}SDA2-Pad59)") (class "Default")
      (node (ref "IC3") (pin "59") (pinfunction "RA3/SDA2_59") (pintype "bidirectional"))
    )
    (net (code "122") (name "unconnected-(IC3-RA4{slash}TDI-Pad60)") (class "Default")
      (node (ref "IC3") (pin "60") (pinfunction "RA4/TDI_60") (pintype "bidirectional"))
    )
    (net (code "123") (name "unconnected-(IC3-RA5{slash}TDO-Pad61)") (class "Default")
      (node (ref "IC3") (pin "61") (pinfunction "RA5/TDO_61") (pintype "bidirectional"))
    )
    (net (code "124") (name "unconnected-(IC3-RA9{slash}VR-{slash}PMA7{slash}CVREF-{slash}AERXD2-Pad28)") (class "Default")
      (node (ref "IC3") (pin "28") (pinfunction "RA9/VR-/PMA7/CVREF-/AERXD2_28") (pintype "bidirectional"))
    )
    (net (code "125") (name "unconnected-(IC3-RA10{slash}VR+{slash}CVREF+{slash}AERXD3{slash}PMA6-Pad29)") (class "Default")
      (node (ref "IC3") (pin "29") (pinfunction "RA10/VR+/CVREF+/AERXD3/PMA6_29") (pintype "bidirectional"))
    )
    (net (code "126") (name "unconnected-(IC3-RB2{slash}AN2{slash}CN4{slash}C2IN--Pad23)") (class "Default")
      (node (ref "IC3") (pin "23") (pinfunction "RB2/AN2/CN4/C2IN-_23") (pintype "bidirectional"))
    )
    (net (code "127") (name "unconnected-(IC3-RB3{slash}AN3{slash}CN5{slash}C2IN+-Pad22)") (class "Default")
      (node (ref "IC3") (pin "22") (pinfunction "RB3/AN3/CN5/C2IN+_22") (pintype "bidirectional"))
    )
    (net (code "128") (name "unconnected-(IC3-RB4{slash}AN4{slash}CN6{slash}C1IN--Pad21)") (class "Default")
      (node (ref "IC3") (pin "21") (pinfunction "RB4/AN4/CN6/C1IN-_21") (pintype "bidirectional"))
    )
    (net (code "129") (name "unconnected-(IC3-RB5{slash}AN5{slash}CN7{slash}C1IN+{slash}VBUSON-Pad20)") (class "Default")
      (node (ref "IC3") (pin "20") (pinfunction "RB5/AN5/CN7/C1IN+/VBUSON_20") (pintype "bidirectional"))
    )
    (net (code "130") (name "unconnected-(IC3-RB6{slash}AN6{slash}PGC2{slash}OCFA-Pad26)") (class "Default")
      (node (ref "IC3") (pin "26") (pinfunction "RB6/AN6/PGC2/OCFA_26") (pintype "bidirectional"))
    )
    (net (code "131") (name "unconnected-(IC3-RB7{slash}AN7{slash}PGD2-Pad27)") (class "Default")
      (node (ref "IC3") (pin "27") (pinfunction "RB7/AN7/PGD2_27") (pintype "bidirectional"))
    )
    (net (code "132") (name "unconnected-(IC3-RB8{slash}AN8{slash}C1OUT-Pad32)") (class "Default")
      (node (ref "IC3") (pin "32") (pinfunction "RB8/AN8/C1OUT_32") (pintype "bidirectional"))
    )
    (net (code "133") (name "unconnected-(IC3-RB9{slash}AN9{slash}C2OUT-Pad33)") (class "Default")
      (node (ref "IC3") (pin "33") (pinfunction "RB9/AN9/C2OUT_33") (pintype "bidirectional"))
    )
    (net (code "134") (name "unconnected-(IC3-RB14{slash}AN14{slash}PMA1{slash}ERXD2{slash}AETXD3{slash}-Pad43)") (class "Default")
      (node (ref "IC3") (pin "43") (pinfunction "RB14/AN14/PMA1/ERXD2/AETXD3/_43") (pintype "bidirectional"))
    )
    (net (code "135") (name "unconnected-(IC3-RE8{slash}INT1{slash}AERXD0-Pad18)") (class "Default")
      (node (ref "IC3") (pin "18") (pinfunction "RE8/INT1/AERXD0_18") (pintype "bidirectional"))
    )
    (net (code "136") (name "unconnected-(IC3-RE9{slash}INT2{slash}AERXD1-Pad19)") (class "Default")
      (node (ref "IC3") (pin "19") (pinfunction "RE9/INT2/AERXD1_19") (pintype "bidirectional"))
    )
    (net (code "137") (name "unconnected-(IC4-CLK2MAC-Pad25)") (class "Default")
      (node (ref "IC4") (pin "25") (pinfunction "CLK2MAC_25") (pintype "bidirectional"))
    )
    (net (code "138") (name "unconnected-(IC4-COL-Pad42)") (class "Default")
      (node (ref "IC4") (pin "42") (pinfunction "COL_42") (pintype "bidirectional"))
    )
    (net (code "139") (name "unconnected-(IC4-LED_SPD-Pad27)") (class "Default")
      (node (ref "IC4") (pin "27") (pinfunction "LED_SPD_27") (pintype "bidirectional"))
    )
    (net (code "140") (name "unconnected-(IC4-RXD_2-Pad45)") (class "Default")
      (node (ref "IC4") (pin "45") (pinfunction "RXD_2_45") (pintype "bidirectional"))
    )
    (net (code "141") (name "unconnected-(IC4-RXD_3-Pad46)") (class "Default")
      (node (ref "IC4") (pin "46") (pinfunction "RXD_3_46") (pintype "bidirectional"))
    )
    (net (code "142") (name "unconnected-(IC4-RX_CLK-Pad38)") (class "Default")
      (node (ref "IC4") (pin "38") (pinfunction "RX_CLK_38") (pintype "bidirectional"))
    )
    (net (code "143") (name "unconnected-(IC4-TCK-Pad8)") (class "Default")
      (node (ref "IC4") (pin "8") (pinfunction "TCK_8") (pintype "input"))
    )
    (net (code "144") (name "unconnected-(IC4-TDI-Pad12)") (class "Default")
      (node (ref "IC4") (pin "12") (pinfunction "TDI_12") (pintype "input"))
    )
    (net (code "145") (name "unconnected-(IC4-TDO-Pad9)") (class "Default")
      (node (ref "IC4") (pin "9") (pinfunction "TDO_9") (pintype "output"))
    )
    (net (code "146") (name "unconnected-(IC4-TMS-Pad10)") (class "Default")
      (node (ref "IC4") (pin "10") (pinfunction "TMS_10") (pintype "input"))
    )
    (net (code "147") (name "unconnected-(IC4-TRST_N-Pad11)") (class "Default")
      (node (ref "IC4") (pin "11") (pinfunction "TRST_N_11") (pintype "input"))
    )
    (net (code "148") (name "unconnected-(IC4-TXD_2-Pad5)") (class "Default")
      (node (ref "IC4") (pin "5") (pinfunction "TXD_2_5") (pintype "bidirectional"))
    )
    (net (code "149") (name "unconnected-(IC4-TX_CLK-Pad1)") (class "Default")
      (node (ref "IC4") (pin "1") (pinfunction "TX_CLK_1") (pintype "bidirectional"))
    )
    (net (code "150") (name "unconnected-(IC4-X2-Pad33)") (class "Default")
      (node (ref "IC4") (pin "33") (pinfunction "X2_33") (pintype "output"))
    )
    (net (code "151") (name "unconnected-(J1-PadRING2)") (class "Default")
      (node (ref "J1") (pin "RING2") (pinfunction "RING2_RING2") (pintype "bidirectional"))
    )
    (net (code "152") (name "unconnected-(JP2-Pad2)") (class "Default")
      (node (ref "JP2") (pin "2") (pinfunction "2_2") (pintype "passive"))
    )
    (net (code "153") (name "unconnected-(JP2-Pad6)") (class "Default")
      (node (ref "JP2") (pin "6") (pinfunction "6_6") (pintype "passive"))
    )
    (net (code "154") (name "unconnected-(JP5-D+-PadD+1)") (class "Default")
      (node (ref "JP5") (pin "D+1") (pinfunction "D+_D+1") (pintype "bidirectional"))
    )
    (net (code "155") (name "unconnected-(JP5-D--PadD-1)") (class "Default")
      (node (ref "JP5") (pin "D-1") (pinfunction "D-_D-1") (pintype "bidirectional"))
    )
    (net (code "156") (name "unconnected-(JP5-ID-PadID1)") (class "Default")
      (node (ref "JP5") (pin "ID1") (pinfunction "ID_ID1") (pintype "bidirectional"))
    )
    (net (code "157") (name "unconnected-(RJ1-PadNC)") (class "Default")
      (node (ref "RJ1") (pin "NC") (pinfunction "NC_NC") (pintype "bidirectional"))
    )
    (net (code "158") (name "unconnected-(SV1-Pad8)") (class "Default")
      (node (ref "SV1") (pin "8") (pinfunction "8_8") (pintype "passive"))
    )
    (net (code "159") (name "unconnected-(U$1-TRI-Pad1)") (class "Default")
      (node (ref "U$1") (pin "1") (pinfunction "TRI_1") (pintype "input"))
    )
    (net (code "160") (name "unconnected-(U$7-TRI-Pad1)") (class "Default")
      (node (ref "U$7") (pin "1") (pinfunction "TRI_1") (pintype "input"))
    )
    (net (code "161") (name "unconnected-(U1-NC-Pad1)") (class "Default")
      (node (ref "U1") (pin "1") (pinfunction "NC_1") (pintype "bidirectional"))
    )
    (net (code "162") (name "unconnected-(U1-RSV-Pad8)") (class "Default")
      (node (ref "U1") (pin "8") (pinfunction "RSV_8") (pintype "bidirectional"))
    )
    (net (code "163") (name "unconnected-(U3A-MICN-Pad2)") (class "Default")
      (node (ref "U3") (pin "2") (pinfunction "MICN_2") (pintype "input"))
    )
    (net (code "164") (name "unconnected-(U3A-TX-Pad27)") (class "Default")
      (node (ref "U3") (pin "27") (pinfunction "TX_27") (pintype "output"))
    )
    (net (code "165") (name "unconnected-(U3A-VCO-Pad15)") (class "Default")
      (node (ref "U3") (pin "15") (pinfunction "VCO_15") (pintype "output"))
    )
  )
)
